# HARDCAL1_REVA_PG3.net
KiCad netlist of a schematic drawn in Altium Designer
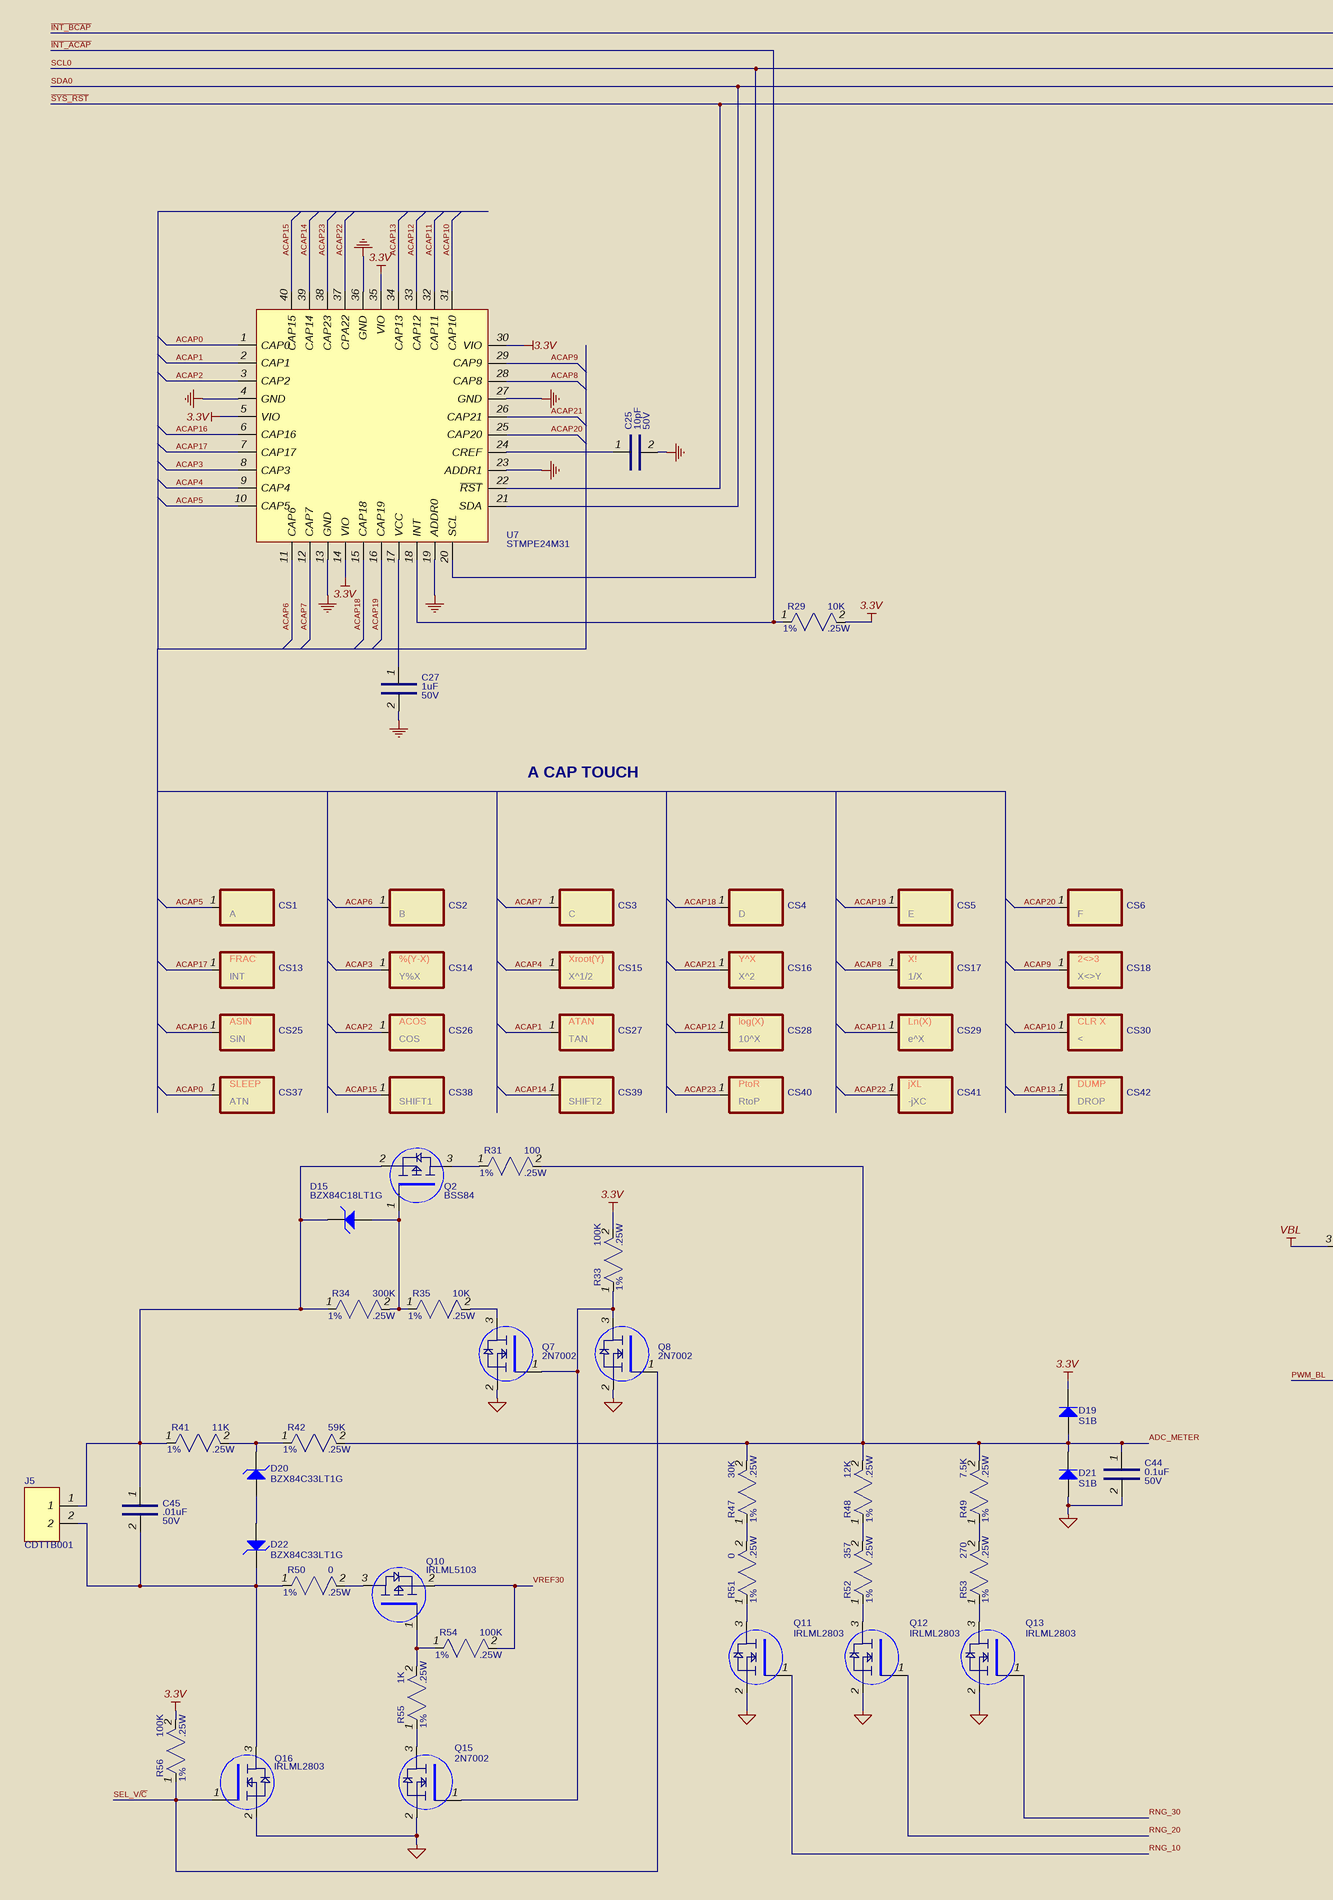
[diagram p0: HARDCAL1_REVA_PG3.SchDoc, left]
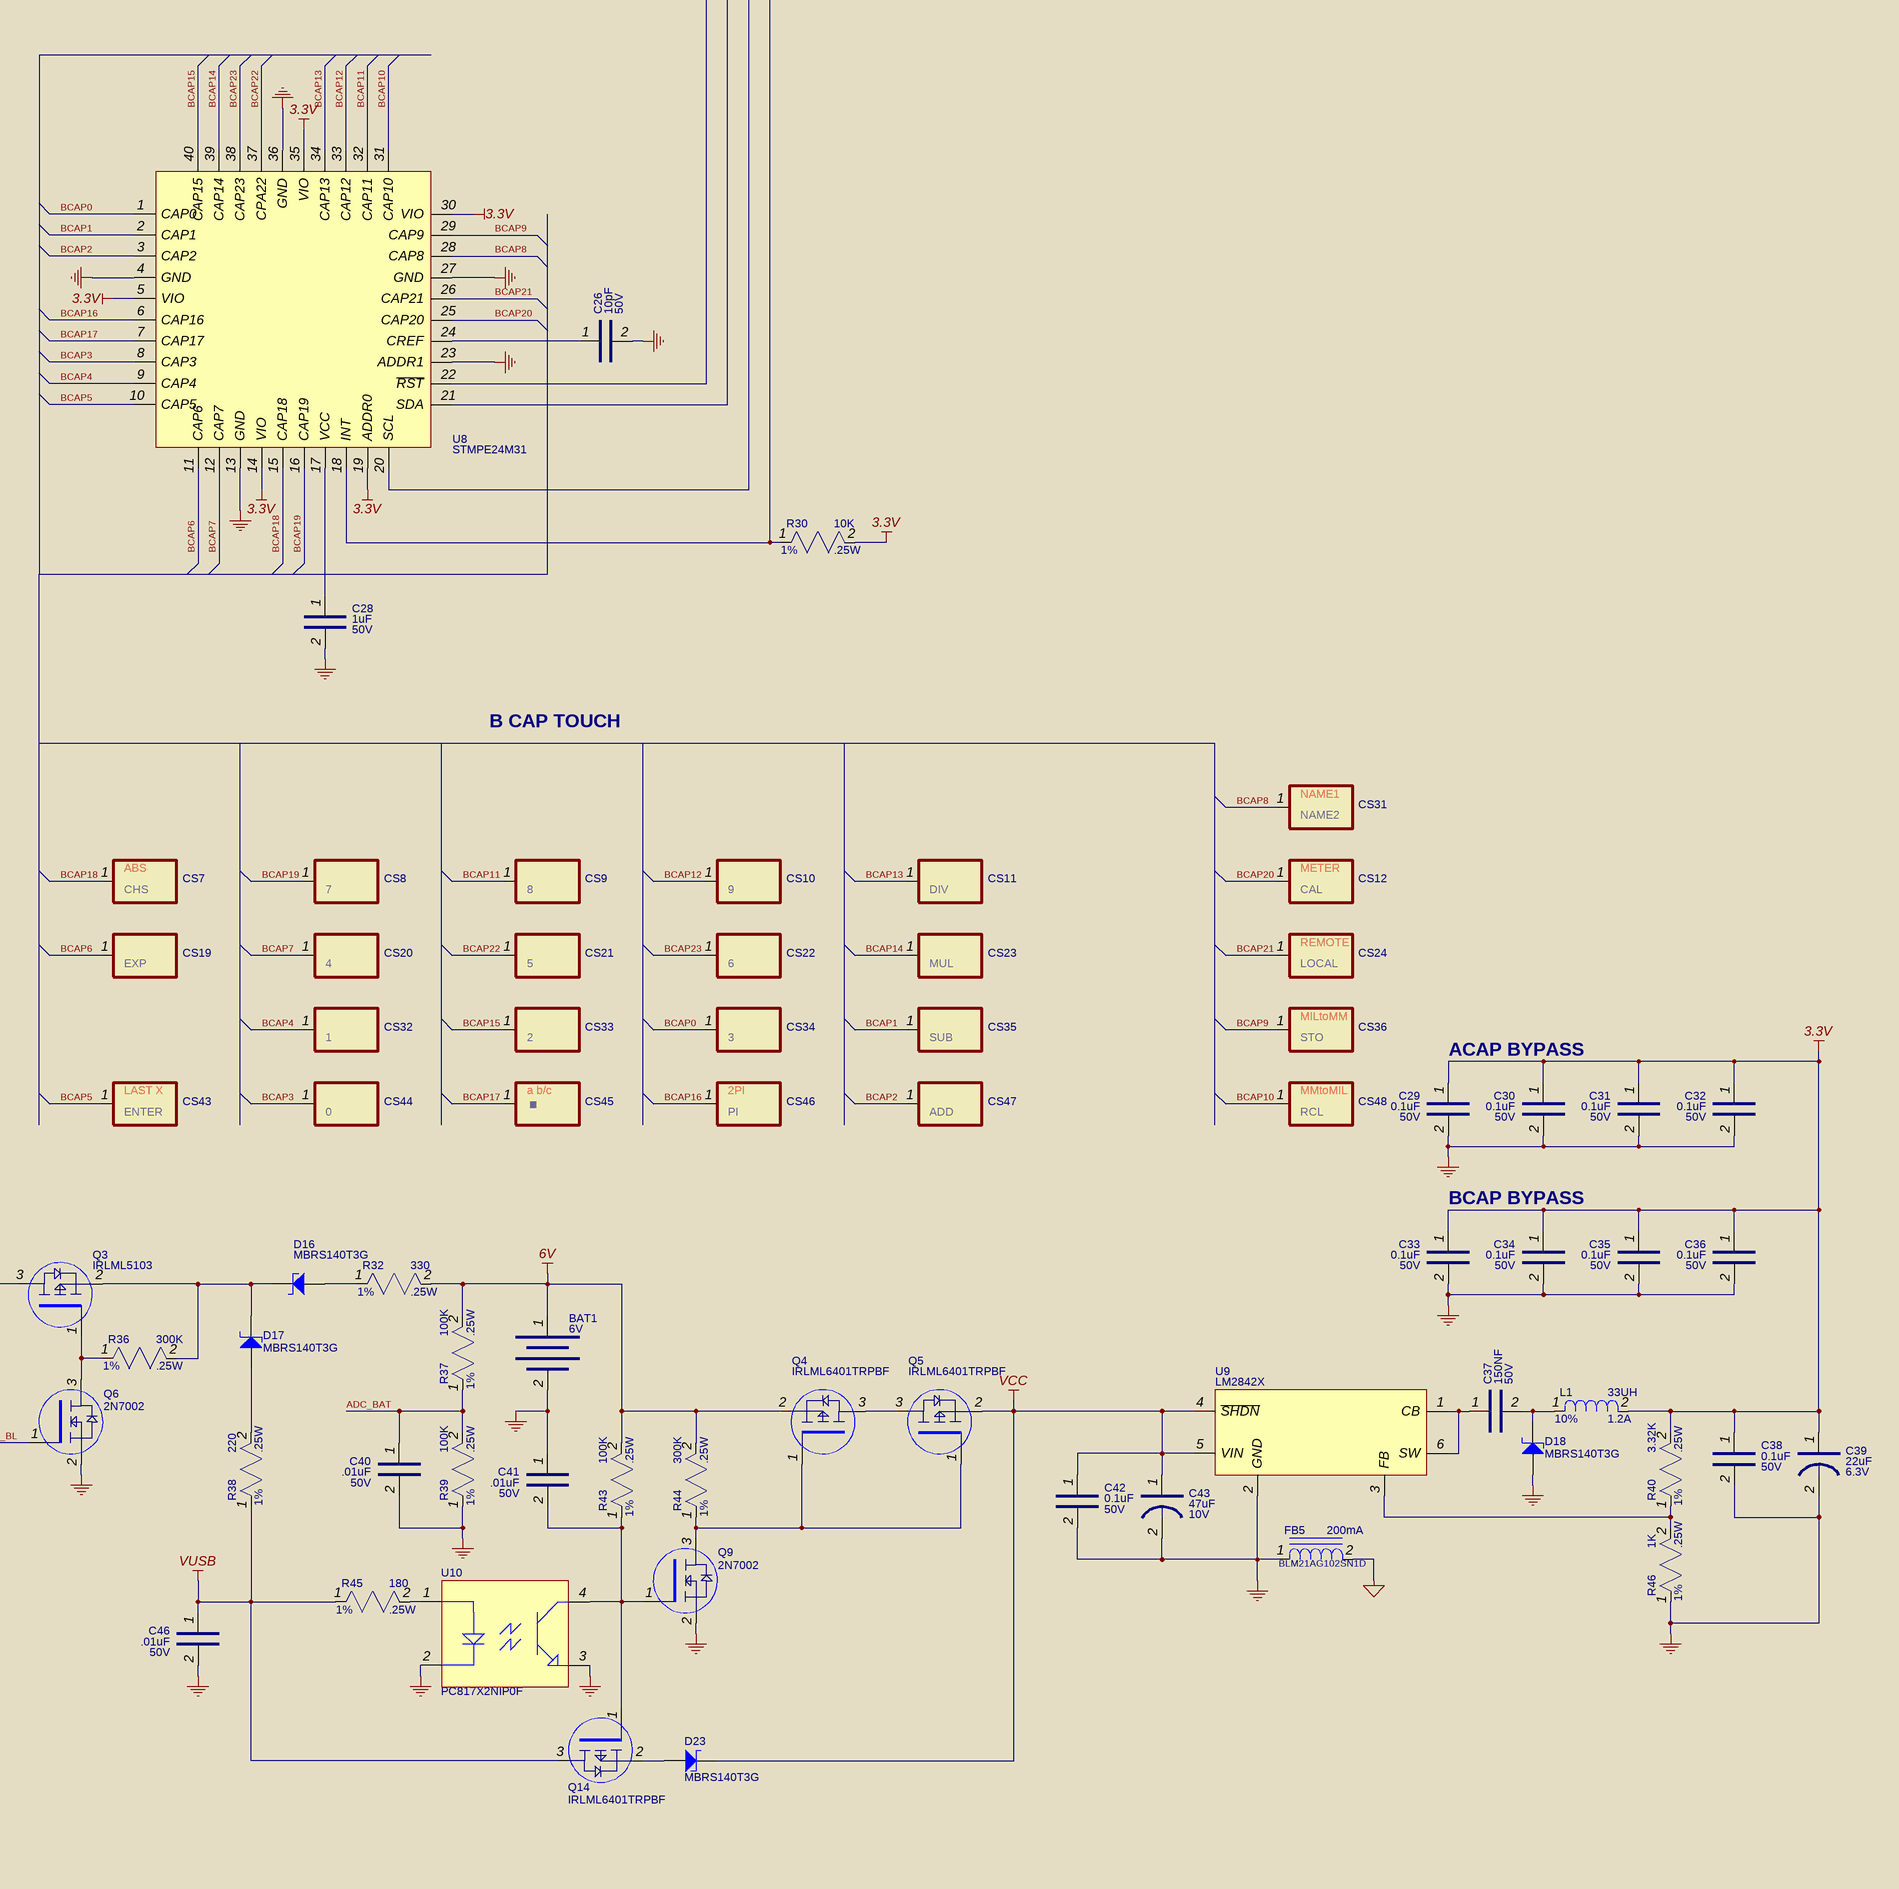
[diagram p1: HARDCAL1_REVA_PG3.SchDoc, right]

(export (version "E")
  (design (tool "Eeschema 10.0.6"))
  (components
    (comp (ref "BAT1")
      (value "CDEVA00082_1")
      (footprint "KEYSTONE_1062")
      (description "CONN, BAT HOLDER 2-COIN CELL 20MM, SMD, ROHS")
      (fields (field (name "MFG") "KEYSTONE ELECTRONICS") (field (name "VOLTAGE") "6V"))
      (libsource (lib "HabLib") (part "CDEVA00082_1"))
    )
    (comp (ref "C25")
      (value "10pF")
      (footprint "3216[1206] - TAN COLOR")
      (description "CAP, CERAMIC, NPO, 10PF, 50V, 1206, 5%, RoHS")
      (fields (field (name "MFG") "AVX") (field (name "TOLERANCE") "10%") (field (name "VOLTAGE") "50V"))
      (libsource (lib "HabLib") (part "CDECA00143"))
    )
    (comp (ref "C26")
      (value "10pF")
      (footprint "3216[1206] - TAN COLOR")
      (description "CAP, CERAMIC, NPO, 10PF, 50V, 1206, 5%, RoHS")
      (fields (field (name "MFG") "AVX") (field (name "TOLERANCE") "10%") (field (name "VOLTAGE") "50V"))
      (libsource (lib "HabLib") (part "CDECA00143"))
    )
    (comp (ref "C27")
      (value "1uF")
      (footprint "3225[1210]")
      (description "CAP, CERAMIC CHIP 1UF 10% 50V X7R ROHS")
      (fields (field (name "MFG") "AVX") (field (name "TOLERANCE") "10%") (field (name "VOLTAGE") "50V"))
      (libsource (lib "HabLib") (part "CDECA00122"))
    )
    (comp (ref "C28")
      (value "1uF")
      (footprint "3225[1210]")
      (description "CAP, CERAMIC CHIP 1UF 10% 50V X7R ROHS")
      (fields (field (name "MFG") "AVX") (field (name "TOLERANCE") "10%") (field (name "VOLTAGE") "50V"))
      (libsource (lib "HabLib") (part "CDECA00122"))
    )
    (comp (ref "C29")
      (value "0.1uF")
      (footprint "3216[1206] - TAN COLOR")
      (description "CAP, CERAMIC CHIP 0.1UF 10% 50V X7R ROHS")
      (fields (field (name "MFG") "AVX") (field (name "TOLERANCE") "10%") (field (name "VOLTAGE") "50V"))
      (libsource (lib "HabLib") (part "CDECA00070"))
    )
    (comp (ref "C30")
      (value "0.1uF")
      (footprint "3216[1206] - TAN COLOR")
      (description "CAP, CERAMIC CHIP 0.1UF 10% 50V X7R ROHS")
      (fields (field (name "MFG") "AVX") (field (name "TOLERANCE") "10%") (field (name "VOLTAGE") "50V"))
      (libsource (lib "HabLib") (part "CDECA00070"))
    )
    (comp (ref "C31")
      (value "0.1uF")
      (footprint "3216[1206] - TAN COLOR")
      (description "CAP, CERAMIC CHIP 0.1UF 10% 50V X7R ROHS")
      (fields (field (name "MFG") "AVX") (field (name "TOLERANCE") "10%") (field (name "VOLTAGE") "50V"))
      (libsource (lib "HabLib") (part "CDECA00070"))
    )
    (comp (ref "C32")
      (value "0.1uF")
      (footprint "3216[1206] - TAN COLOR")
      (description "CAP, CERAMIC CHIP 0.1UF 10% 50V X7R ROHS")
      (fields (field (name "MFG") "AVX") (field (name "TOLERANCE") "10%") (field (name "VOLTAGE") "50V"))
      (libsource (lib "HabLib") (part "CDECA00070"))
    )
    (comp (ref "C33")
      (value "0.1uF")
      (footprint "3216[1206] - TAN COLOR")
      (description "CAP, CERAMIC CHIP 0.1UF 10% 50V X7R ROHS")
      (fields (field (name "MFG") "AVX") (field (name "TOLERANCE") "10%") (field (name "VOLTAGE") "50V"))
      (libsource (lib "HabLib") (part "CDECA00070"))
    )
    (comp (ref "C34")
      (value "0.1uF")
      (footprint "3216[1206] - TAN COLOR")
      (description "CAP, CERAMIC CHIP 0.1UF 10% 50V X7R ROHS")
      (fields (field (name "MFG") "AVX") (field (name "TOLERANCE") "10%") (field (name "VOLTAGE") "50V"))
      (libsource (lib "HabLib") (part "CDECA00070"))
    )
    (comp (ref "C35")
      (value "0.1uF")
      (footprint "3216[1206] - TAN COLOR")
      (description "CAP, CERAMIC CHIP 0.1UF 10% 50V X7R ROHS")
      (fields (field (name "MFG") "AVX") (field (name "TOLERANCE") "10%") (field (name "VOLTAGE") "50V"))
      (libsource (lib "HabLib") (part "CDECA00070"))
    )
    (comp (ref "C36")
      (value "0.1uF")
      (footprint "3216[1206] - TAN COLOR")
      (description "CAP, CERAMIC CHIP 0.1UF 10% 50V X7R ROHS")
      (fields (field (name "MFG") "AVX") (field (name "TOLERANCE") "10%") (field (name "VOLTAGE") "50V"))
      (libsource (lib "HabLib") (part "CDECA00070"))
    )
    (comp (ref "C37")
      (value "150NF")
      (footprint "3216[1206] - TAN COLOR")
      (description "CAP, CERAMIC, X7R, 150NF, 50V, 1206, 10%, RoHS")
      (fields (field (name "MFG") "KEMET") (field (name "TOLERANCE") "10%") (field (name "VOLTAGE") "50V"))
      (libsource (lib "HabLib") (part "CDECA00143_1"))
    )
    (comp (ref "C38")
      (value "0.1uF")
      (footprint "3216[1206] - TAN COLOR")
      (description "CAP, CERAMIC CHIP 0.1UF 10% 50V X7R ROHS")
      (fields (field (name "MFG") "AVX") (field (name "TOLERANCE") "10%") (field (name "VOLTAGE") "50V"))
      (libsource (lib "HabLib") (part "CDECA00070"))
    )
    (comp (ref "C39")
      (value "22uF")
      (footprint "3216[1206] - TANTALUM")
      (description "CAP, TANT, 22UF, 6.3V, 20%, LOW ESR, 1206ROHS")
      (fields (field (name "MFG") "AVX") (field (name "TOLERANCE") "20%") (field (name "VOLTAGE") "6.3V"))
      (libsource (lib "HabLib") (part "CDECA00139_1"))
    )
    (comp (ref "C40")
      (value ".01uF")
      (footprint "3216[1206] - TAN COLOR")
      (description "CAP, CERAMIC CHIP 0.01UF 10% 50V X7R ROHS")
      (fields
        (field (name "MFG") "PANASONIC")
        (field (name "TOLERANCE") "10%")
        (field (name "VOLTAGE") "50V")
      )
      (libsource (lib "HabLib") (part "CDECA00085"))
    )
    (comp (ref "C41")
      (value ".01uF")
      (footprint "3216[1206] - TAN COLOR")
      (description "CAP, CERAMIC CHIP 0.01UF 10% 50V X7R ROHS")
      (fields
        (field (name "MFG") "PANASONIC")
        (field (name "TOLERANCE") "10%")
        (field (name "VOLTAGE") "50V")
      )
      (libsource (lib "HabLib") (part "CDECA00085"))
    )
    (comp (ref "C42")
      (value "0.1uF")
      (footprint "3216[1206] - TAN COLOR")
      (description "CAP, CERAMIC CHIP 0.1UF 10% 50V X7R ROHS")
      (fields (field (name "MFG") "AVX") (field (name "TOLERANCE") "10%") (field (name "VOLTAGE") "50V"))
      (libsource (lib "HabLib") (part "CDECA00070"))
    )
    (comp (ref "C43")
      (value "47uF")
      (footprint "CAP_TANT_3528")
      (description "CAP, TANT, 47UF, 25V, 20%, 3528 ROHS")
      (fields (field (name "MFG") "AVX") (field (name "TOLERANCE") "20%") (field (name "VOLTAGE") "10V"))
      (libsource (lib "HabLib") (part "CDECA00110_1"))
    )
    (comp (ref "C44")
      (value "0.1uF")
      (footprint "3216[1206] - TAN COLOR")
      (description "CAP, CERAMIC CHIP 0.1UF 10% 50V X7R ROHS")
      (fields (field (name "MFG") "AVX") (field (name "TOLERANCE") "10%") (field (name "VOLTAGE") "50V"))
      (libsource (lib "HabLib") (part "CDECA00070"))
    )
    (comp (ref "C45")
      (value ".01uF")
      (footprint "3216[1206] - TAN COLOR")
      (description "CAP, CERAMIC CHIP 0.01UF 10% 50V X7R ROHS")
      (fields
        (field (name "MFG") "PANASONIC")
        (field (name "TOLERANCE") "10%")
        (field (name "VOLTAGE") "50V")
      )
      (libsource (lib "") (part "CDECA00085_1"))
    )
    (comp (ref "C46")
      (value ".01uF")
      (footprint "3216[1206] - TAN COLOR")
      (description "CAP, CERAMIC CHIP 0.01UF 10% 50V X7R ROHS")
      (fields
        (field (name "MFG") "PANASONIC")
        (field (name "TOLERANCE") "10%")
        (field (name "VOLTAGE") "50V")
      )
      (libsource (lib "HabLib") (part "CDECA00085"))
    )
    (comp (ref "CS1")
      (value "CAP_SENSOR")
      (footprint "CAPTOUCH1_10X10")
      (description "CAP SENSOR FOR PCB")
      (fields (field (name "VALUE2") "A") (field (name "PUBLISHER") "Altium Limited"))
      (libsource (lib "HabLib") (part "CAP_SENSOR"))
    )
    (comp (ref "CS2")
      (value "CAP_SENSOR")
      (footprint "CAPTOUCH1_10X10")
      (description "CAP SENSOR FOR PCB")
      (fields (field (name "VALUE2") "B") (field (name "PUBLISHER") "Altium Limited"))
      (libsource (lib "HabLib") (part "CAP_SENSOR"))
    )
    (comp (ref "CS3")
      (value "CAP_SENSOR")
      (footprint "CAPTOUCH1_10X10")
      (description "CAP SENSOR FOR PCB")
      (fields (field (name "VALUE2") "C") (field (name "PUBLISHER") "Altium Limited"))
      (libsource (lib "HabLib") (part "CAP_SENSOR"))
    )
    (comp (ref "CS4")
      (value "CAP_SENSOR")
      (footprint "CAPTOUCH1_10X10")
      (description "CAP SENSOR FOR PCB")
      (fields (field (name "VALUE2") "D") (field (name "PUBLISHER") "Altium Limited"))
      (libsource (lib "HabLib") (part "CAP_SENSOR"))
    )
    (comp (ref "CS5")
      (value "CAP_SENSOR")
      (footprint "CAPTOUCH1_10X10")
      (description "CAP SENSOR FOR PCB")
      (fields (field (name "VALUE2") "E") (field (name "PUBLISHER") "Altium Limited"))
      (libsource (lib "HabLib") (part "CAP_SENSOR"))
    )
    (comp (ref "CS6")
      (value "CAP_SENSOR")
      (footprint "CAPTOUCH1_10X10")
      (description "CAP SENSOR FOR PCB")
      (fields (field (name "VALUE2") "F") (field (name "PUBLISHER") "Altium Limited"))
      (libsource (lib "HabLib") (part "CAP_SENSOR"))
    )
    (comp (ref "CS7")
      (value "ABS")
      (footprint "CAPTOUCH1_10X10")
      (description "CAP SENSOR FOR PCB")
      (fields
        (field (name "VALUE2") "CHS")
        (field (name "Comment") "CAP_SENSOR")
        (field (name "PUBLISHER") "Altium Limited")
      )
      (libsource (lib "HabLib") (part "CAP_SENSOR"))
    )
    (comp (ref "CS8")
      (value "CAP_SENSOR")
      (footprint "CAPTOUCH1_10X10")
      (description "CAP SENSOR FOR PCB")
      (fields (field (name "VALUE2") "7") (field (name "PUBLISHER") "Altium Limited"))
      (libsource (lib "HabLib") (part "CAP_SENSOR"))
    )
    (comp (ref "CS9")
      (value "CAP_SENSOR")
      (footprint "CAPTOUCH1_10X10")
      (description "CAP SENSOR FOR PCB")
      (fields (field (name "VALUE2") "8") (field (name "PUBLISHER") "Altium Limited"))
      (libsource (lib "HabLib") (part "CAP_SENSOR"))
    )
    (comp (ref "CS10")
      (value "CAP_SENSOR")
      (footprint "CAPTOUCH1_10X10")
      (description "CAP SENSOR FOR PCB")
      (fields (field (name "VALUE2") "9") (field (name "PUBLISHER") "Altium Limited"))
      (libsource (lib "HabLib") (part "CAP_SENSOR"))
    )
    (comp (ref "CS11")
      (value "CAP_SENSOR")
      (footprint "CAPTOUCH1_10X10")
      (description "CAP SENSOR FOR PCB")
      (fields (field (name "VALUE2") "DIV") (field (name "PUBLISHER") "Altium Limited"))
      (libsource (lib "HabLib") (part "CAP_SENSOR"))
    )
    (comp (ref "CS12")
      (value "METER")
      (footprint "CAPTOUCH1_10X10")
      (description "CAP SENSOR FOR PCB")
      (fields
        (field (name "VALUE2") "CAL")
        (field (name "Comment") "CAP_SENSOR")
        (field (name "PUBLISHER") "Altium Limited")
      )
      (libsource (lib "HabLib") (part "CAP_SENSOR"))
    )
    (comp (ref "CS13")
      (value "FRAC")
      (footprint "CAPTOUCH1_10X10")
      (description "CAP SENSOR FOR PCB")
      (fields
        (field (name "VALUE2") "INT")
        (field (name "Comment") "CAP_SENSOR")
        (field (name "PUBLISHER") "Altium Limited")
      )
      (libsource (lib "HabLib") (part "CAP_SENSOR"))
    )
    (comp (ref "CS14")
      (value "%(Y-X)")
      (footprint "CAPTOUCH1_10X10")
      (description "CAP SENSOR FOR PCB")
      (fields
        (field (name "VALUE2") "Y%X")
        (field (name "Comment") "CAP_SENSOR")
        (field (name "PUBLISHER") "Altium Limited")
      )
      (libsource (lib "HabLib") (part "CAP_SENSOR"))
    )
    (comp (ref "CS15")
      (value "Xroot(Y)")
      (footprint "CAPTOUCH1_10X10")
      (description "CAP SENSOR FOR PCB")
      (fields
        (field (name "VALUE2") "X^1/2")
        (field (name "Comment") "CAP_SENSOR")
        (field (name "PUBLISHER") "Altium Limited")
      )
      (libsource (lib "HabLib") (part "CAP_SENSOR"))
    )
    (comp (ref "CS16")
      (value "Y^X")
      (footprint "CAPTOUCH1_10X10")
      (description "CAP SENSOR FOR PCB")
      (fields
        (field (name "VALUE2") "X^2")
        (field (name "Comment") "CAP_SENSOR")
        (field (name "PUBLISHER") "Altium Limited")
      )
      (libsource (lib "HabLib") (part "CAP_SENSOR"))
    )
    (comp (ref "CS17")
      (value "X!")
      (footprint "CAPTOUCH1_10X10")
      (description "CAP SENSOR FOR PCB")
      (fields
        (field (name "VALUE2") "1/X")
        (field (name "Comment") "CAP_SENSOR")
        (field (name "PUBLISHER") "Altium Limited")
      )
      (libsource (lib "HabLib") (part "CAP_SENSOR"))
    )
    (comp (ref "CS18")
      (value "2<>3")
      (footprint "CAPTOUCH1_10X10")
      (description "CAP SENSOR FOR PCB")
      (fields
        (field (name "VALUE2") "X<>Y")
        (field (name "Comment") "CAP_SENSOR")
        (field (name "PUBLISHER") "Altium Limited")
      )
      (libsource (lib "HabLib") (part "CAP_SENSOR"))
    )
    (comp (ref "CS19")
      (value "CAP_SENSOR")
      (footprint "CAPTOUCH1_10X10")
      (description "CAP SENSOR FOR PCB")
      (fields (field (name "VALUE2") "EXP") (field (name "PUBLISHER") "Altium Limited"))
      (libsource (lib "HabLib") (part "CAP_SENSOR"))
    )
    (comp (ref "CS20")
      (value "CAP_SENSOR")
      (footprint "CAPTOUCH1_10X10")
      (description "CAP SENSOR FOR PCB")
      (fields (field (name "VALUE2") "4") (field (name "PUBLISHER") "Altium Limited"))
      (libsource (lib "HabLib") (part "CAP_SENSOR"))
    )
    (comp (ref "CS21")
      (value "CAP_SENSOR")
      (footprint "CAPTOUCH1_10X10")
      (description "CAP SENSOR FOR PCB")
      (fields (field (name "VALUE2") "5") (field (name "PUBLISHER") "Altium Limited"))
      (libsource (lib "HabLib") (part "CAP_SENSOR"))
    )
    (comp (ref "CS22")
      (value "CAP_SENSOR")
      (footprint "CAPTOUCH1_10X10")
      (description "CAP SENSOR FOR PCB")
      (fields (field (name "VALUE2") "6") (field (name "PUBLISHER") "Altium Limited"))
      (libsource (lib "HabLib") (part "CAP_SENSOR"))
    )
    (comp (ref "CS23")
      (value "CAP_SENSOR")
      (footprint "CAPTOUCH1_10X10")
      (description "CAP SENSOR FOR PCB")
      (fields (field (name "VALUE2") "MUL") (field (name "PUBLISHER") "Altium Limited"))
      (libsource (lib "HabLib") (part "CAP_SENSOR"))
    )
    (comp (ref "CS24")
      (value "REMOTE")
      (footprint "CAPTOUCH1_10X10")
      (description "CAP SENSOR FOR PCB")
      (fields
        (field (name "VALUE2") "LOCAL")
        (field (name "Comment") "CAP_SENSOR")
        (field (name "PUBLISHER") "Altium Limited")
      )
      (libsource (lib "HabLib") (part "CAP_SENSOR"))
    )
    (comp (ref "CS25")
      (value "ASIN")
      (footprint "CAPTOUCH1_10X10")
      (description "CAP SENSOR FOR PCB")
      (fields
        (field (name "VALUE2") "SIN")
        (field (name "Comment") "CAP_SENSOR")
        (field (name "PUBLISHER") "Altium Limited")
      )
      (libsource (lib "HabLib") (part "CAP_SENSOR"))
    )
    (comp (ref "CS26")
      (value "ACOS")
      (footprint "CAPTOUCH1_10X10")
      (description "CAP SENSOR FOR PCB")
      (fields
        (field (name "VALUE2") "COS")
        (field (name "Comment") "CAP_SENSOR")
        (field (name "PUBLISHER") "Altium Limited")
      )
      (libsource (lib "HabLib") (part "CAP_SENSOR"))
    )
    (comp (ref "CS27")
      (value "ATAN")
      (footprint "CAPTOUCH1_10X10")
      (description "CAP SENSOR FOR PCB")
      (fields
        (field (name "VALUE2") "TAN")
        (field (name "Comment") "CAP_SENSOR")
        (field (name "PUBLISHER") "Altium Limited")
      )
      (libsource (lib "HabLib") (part "CAP_SENSOR"))
    )
    (comp (ref "CS28")
      (value "log(X)")
      (footprint "CAPTOUCH1_10X10")
      (description "CAP SENSOR FOR PCB")
      (fields
        (field (name "VALUE2") "10^X")
        (field (name "Comment") "CAP_SENSOR")
        (field (name "PUBLISHER") "Altium Limited")
      )
      (libsource (lib "HabLib") (part "CAP_SENSOR"))
    )
    (comp (ref "CS29")
      (value "Ln(X)")
      (footprint "CAPTOUCH1_10X10")
      (description "CAP SENSOR FOR PCB")
      (fields
        (field (name "VALUE2") "e^X")
        (field (name "Comment") "CAP_SENSOR")
        (field (name "PUBLISHER") "Altium Limited")
      )
      (libsource (lib "HabLib") (part "CAP_SENSOR"))
    )
    (comp (ref "CS30")
      (value "CLR X")
      (footprint "CAPTOUCH1_10X10")
      (description "CAP SENSOR FOR PCB")
      (fields
        (field (name "VALUE2") "<")
        (field (name "Comment") "CAP_SENSOR")
        (field (name "PUBLISHER") "Altium Limited")
      )
      (libsource (lib "HabLib") (part "CAP_SENSOR"))
    )
    (comp (ref "CS31")
      (value "NAME1")
      (footprint "CAPTOUCH1_10X10")
      (description "CAP SENSOR FOR PCB")
      (fields
        (field (name "VALUE2") "NAME2")
        (field (name "Comment") "CAP_SENSOR")
        (field (name "PUBLISHER") "Altium Limited")
      )
      (libsource (lib "HabLib") (part "CAP_SENSOR"))
    )
    (comp (ref "CS32")
      (value "CAP_SENSOR")
      (footprint "CAPTOUCH1_10X10")
      (description "CAP SENSOR FOR PCB")
      (fields (field (name "VALUE2") "1") (field (name "PUBLISHER") "Altium Limited"))
      (libsource (lib "HabLib") (part "CAP_SENSOR"))
    )
    (comp (ref "CS33")
      (value "CAP_SENSOR")
      (footprint "CAPTOUCH1_10X10")
      (description "CAP SENSOR FOR PCB")
      (fields (field (name "VALUE2") "2") (field (name "PUBLISHER") "Altium Limited"))
      (libsource (lib "HabLib") (part "CAP_SENSOR"))
    )
    (comp (ref "CS34")
      (value "CAP_SENSOR")
      (footprint "CAPTOUCH1_10X10")
      (description "CAP SENSOR FOR PCB")
      (fields (field (name "VALUE2") "3") (field (name "PUBLISHER") "Altium Limited"))
      (libsource (lib "HabLib") (part "CAP_SENSOR"))
    )
    (comp (ref "CS35")
      (value "CAP_SENSOR")
      (footprint "CAPTOUCH1_10X10")
      (description "CAP SENSOR FOR PCB")
      (fields (field (name "VALUE2") "SUB") (field (name "PUBLISHER") "Altium Limited"))
      (libsource (lib "HabLib") (part "CAP_SENSOR"))
    )
    (comp (ref "CS36")
      (value "MILtoMM")
      (footprint "CAPTOUCH1_10X10")
      (description "CAP SENSOR FOR PCB")
      (fields
        (field (name "VALUE2") "STO")
        (field (name "Comment") "CAP_SENSOR")
        (field (name "PUBLISHER") "Altium Limited")
      )
      (libsource (lib "HabLib") (part "CAP_SENSOR"))
    )
    (comp (ref "CS37")
      (value "SLEEP")
      (footprint "CAPTOUCH1_10X10")
      (description "CAP SENSOR FOR PCB")
      (fields
        (field (name "VALUE2") "ATN")
        (field (name "Comment") "CAP_SENSOR")
        (field (name "PUBLISHER") "Altium Limited")
      )
      (libsource (lib "HabLib") (part "CAP_SENSOR"))
    )
    (comp (ref "CS38")
      (value "CAP_SENSOR")
      (footprint "CAPTOUCH1_10X10")
      (description "CAP SENSOR FOR PCB")
      (fields (field (name "VALUE2") "SHIFT1") (field (name "PUBLISHER") "Altium Limited"))
      (libsource (lib "HabLib") (part "CAP_SENSOR"))
    )
    (comp (ref "CS39")
      (value "CAP_SENSOR")
      (footprint "CAPTOUCH1_10X10")
      (description "CAP SENSOR FOR PCB")
      (fields (field (name "VALUE2") "SHIFT2") (field (name "PUBLISHER") "Altium Limited"))
      (libsource (lib "HabLib") (part "CAP_SENSOR"))
    )
    (comp (ref "CS40")
      (value "PtoR")
      (footprint "CAPTOUCH1_10X10")
      (description "CAP SENSOR FOR PCB")
      (fields
        (field (name "VALUE2") "RtoP")
        (field (name "Comment") "CAP_SENSOR")
        (field (name "PUBLISHER") "Altium Limited")
      )
      (libsource (lib "HabLib") (part "CAP_SENSOR"))
    )
    (comp (ref "CS41")
      (value "jXL")
      (footprint "CAPTOUCH1_10X10")
      (description "CAP SENSOR FOR PCB")
      (fields
        (field (name "VALUE2") "-jXC")
        (field (name "Comment") "CAP_SENSOR")
        (field (name "PUBLISHER") "Altium Limited")
      )
      (libsource (lib "HabLib") (part "CAP_SENSOR"))
    )
    (comp (ref "CS42")
      (value "DUMP")
      (footprint "CAPTOUCH1_10X10")
      (description "CAP SENSOR FOR PCB")
      (fields
        (field (name "VALUE2") "DROP")
        (field (name "Comment") "CAP_SENSOR")
        (field (name "PUBLISHER") "Altium Limited")
      )
      (libsource (lib "HabLib") (part "CAP_SENSOR"))
    )
    (comp (ref "CS43")
      (value "LAST X")
      (footprint "CAPTOUCH1_10X23")
      (description "CAP SENSOR FOR PCB")
      (fields
        (field (name "VALUE2") "ENTER")
        (field (name "Comment") "CAP_SENSOR_ENT")
        (field (name "PUBLISHER") "Altium Limited")
      )
      (libsource (lib "HabLib") (part "CAP_SENSOR_ENT"))
    )
    (comp (ref "CS44")
      (value "CAP_SENSOR")
      (footprint "CAPTOUCH1_10X10")
      (description "CAP SENSOR FOR PCB")
      (fields (field (name "VALUE2") "0") (field (name "PUBLISHER") "Altium Limited"))
      (libsource (lib "HabLib") (part "CAP_SENSOR"))
    )
    (comp (ref "CS45")
      (value "a b/c")
      (footprint "CAPTOUCH1_10X10")
      (description "CAP SENSOR FOR PCB")
      (fields
        (field (name "VALUE2") ".")
        (field (name "Comment") "CAP_SENSOR")
        (field (name "PUBLISHER") "Altium Limited")
      )
      (libsource (lib "HabLib") (part "CAP_SENSOR"))
    )
    (comp (ref "CS46")
      (value "2PI")
      (footprint "CAPTOUCH1_10X10")
      (description "CAP SENSOR FOR PCB")
      (fields
        (field (name "VALUE2") "PI")
        (field (name "Comment") "CAP_SENSOR")
        (field (name "PUBLISHER") "Altium Limited")
      )
      (libsource (lib "HabLib") (part "CAP_SENSOR"))
    )
    (comp (ref "CS47")
      (value "CAP_SENSOR")
      (footprint "CAPTOUCH1_10X10")
      (description "CAP SENSOR FOR PCB")
      (fields (field (name "VALUE2") "ADD") (field (name "PUBLISHER") "Altium Limited"))
      (libsource (lib "HabLib") (part "CAP_SENSOR"))
    )
    (comp (ref "CS48")
      (value "MMtoMIL")
      (footprint "CAPTOUCH1_10X10")
      (description "CAP SENSOR FOR PCB")
      (fields
        (field (name "VALUE2") "RCL")
        (field (name "Comment") "CAP_SENSOR")
        (field (name "PUBLISHER") "Altium Limited")
      )
      (libsource (lib "HabLib") (part "CAP_SENSOR"))
    )
    (comp (ref "D15")
      (value "BZX84C18LT1G")
      (footprint "SOT23 - TRANSISTOR")
      (description "DIODE, ZENER, 18V, 225MW, SOT-23, ROHS")
      (fields (field (name "MFG") "ON SEMICONDUCTOR") (field (name "Comment") "CDEDA00055_1"))
      (libsource (lib "HabLib") (part "CDEDA00055_1"))
    )
    (comp (ref "D16")
      (value "MBRS140T3G")
      (footprint "DIODE_SMB")
      (description "Diode, Schottky rectifier, 40V, 1A, SMB package, Pb free")
      (fields
        (field (name "MFG") "ON SEMICONDUCTOR")
        (field (name "Comment") "CDEDA00019")
        (field (name "PUBLISHER") "Altium Limited")
      )
      (libsource (lib "HabLib") (part "CDEDA00019"))
    )
    (comp (ref "D17")
      (value "MBRS140T3G")
      (footprint "DIODE_SMB")
      (description "Diode, Schottky rectifier, 40V, 1A, SMB package, Pb free")
      (fields
        (field (name "MFG") "ON SEMICONDUCTOR")
        (field (name "Comment") "CDEDA00019")
        (field (name "PUBLISHER") "Altium Limited")
      )
      (libsource (lib "HabLib") (part "CDEDA00019"))
    )
    (comp (ref "D18")
      (value "MBRS140T3G")
      (footprint "DIODE_SMB")
      (description "Diode, Schottky rectifier, 40V, 1A, SMB package, Pb free")
      (fields
        (field (name "MFG") "ON SEMICONDUCTOR")
        (field (name "Comment") "CDEDA00019")
        (field (name "PUBLISHER") "Altium Limited")
      )
      (libsource (lib "HabLib") (part "CDEDA00019"))
    )
    (comp (ref "D19")
      (value "S1B")
      (footprint "DIODE SMA")
      (description "DIODE, 1A, 100V, SMA, ROHS")
      (fields (field (name "MFG") "FAIRCHILD SEMICONDUCTOR") (field (name "Comment") "CDEDA00055_3"))
      (libsource (lib "HabLib") (part "CDEDA00055_3"))
    )
    (comp (ref "D20")
      (value "BZX84C33LT1G")
      (footprint "SOT23 - TRANSISTOR")
      (description "DIODE, ZENER, 33V, 225MW, SOT-23, ROHS")
      (fields (field (name "MFG") "ON SEMICONDUCTOR") (field (name "Comment") "CDEDA00055_2"))
      (libsource (lib "HabLib") (part "CDEDA00055_2"))
    )
    (comp (ref "D21")
      (value "S1B")
      (footprint "DIODE SMA")
      (description "DIODE, 1A, 100V, SMA, ROHS")
      (fields (field (name "MFG") "FAIRCHILD SEMICONDUCTOR") (field (name "Comment") "CDEDA00055_3"))
      (libsource (lib "HabLib") (part "CDEDA00055_3"))
    )
    (comp (ref "D22")
      (value "BZX84C33LT1G")
      (footprint "SOT23 - TRANSISTOR")
      (description "DIODE, ZENER, 33V, 225MW, SOT-23, ROHS")
      (fields (field (name "MFG") "ON SEMICONDUCTOR") (field (name "Comment") "CDEDA00055_2"))
      (libsource (lib "HabLib") (part "CDEDA00055_2"))
    )
    (comp (ref "D23")
      (value "MBRS140T3G")
      (footprint "DIODE_SMB")
      (description "Diode, Schottky rectifier, 40V, 1A, SMB package, Pb free")
      (fields
        (field (name "MFG") "ON SEMICONDUCTOR")
        (field (name "Comment") "CDEDA00019")
        (field (name "PUBLISHER") "Altium Limited")
      )
      (libsource (lib "HabLib") (part "CDEDA00019"))
    )
    (comp (ref "FB5")
      (value "CDEVA00115")
      (footprint "2012[0805]")
      (description "FERRITE, 1KOHM AT 100MHZ, 220MA, .450DCR")
      (fields
        (field (name "MFG") "MURATA")
        (field (name "TOLERANCE") "10%")
        (field (name "MFG_PN") "BLM21AG102SN1D")
        (field (name "POWER") "200mA")
        (field (name "PUBLISHER") "Altium Limited")
      )
      (libsource (lib "HabLib") (part "CDEVA00115"))
    )
    (comp (ref "J5")
      (value "CDTTB001")
      (footprint "PHOENIX_CONTACT_1933189")
      (description "CONN, HDR, 2PIN, 5MM PHONIX CONTACT, ROHS")
      (fields (field (name "MFG") "PHOENIX CONTACT"))
      (libsource (lib "HabLib") (part "CDTTB001"))
    )
    (comp (ref "L1")
      (value "33UH")
      (footprint "BOURNS_SDR0805-XXXX")
      (description "INDUCTOR, 33UH, 10%, SMT, NON-SHIELDED, FERRITE CORE, ROHS")
      (fields
        (field (name "MFG") "BOURNS")
        (field (name "TOLERANCE") "10%")
        (field (name "POWER") "1.2A")
        (field (name "Comment") "CDEHA00005_1")
      )
      (libsource (lib "HabLib") (part "CDEHA00005_1"))
    )
    (comp (ref "Q2")
      (value "BSS84")
      (footprint "SOT23 - TRANSISTOR")
      (description "MOSFET P CHN, VDS=50V, RDSON = 10OHM, SOT 23")
      (fields
        (field (name "MFG") "DIODES INC")
        (field (name "Comment") "CDENA00031_1")
        (field (name "PUBLISHER") "Altium Limited")
      )
      (libsource (lib "HabLib") (part "CDENA00031_1"))
    )
    (comp (ref "Q3")
      (value "IRLML5103")
      (footprint "SOT23 - TRANSISTOR")
      (description "MOSFET P CHN, VDS=30V, RDSON = .6OHM, SOT 23")
      (fields
        (field (name "MFG") "INTERNATIONAL RECTIFIER")
        (field (name "Comment") "CDENA00031")
        (field (name "PUBLISHER") "Altium Limited")
      )
      (libsource (lib "HabLib") (part "CDENA00031"))
    )
    (comp (ref "Q4")
      (value "IRLML6401TRPBF")
      (footprint "SOT23 - TRANSISTOR")
      (description "MOSFET P CHN, VDS=12V, RDSON = .05OHM, SOT 23")
      (fields
        (field (name "MFG") "INTERNATIONAL RECTIFIER")
        (field (name "Comment") "CDENA00031_3")
        (field (name "PUBLISHER") "Altium Limited")
      )
      (libsource (lib "HabLib") (part "CDENA00031_3"))
    )
    (comp (ref "Q5")
      (value "IRLML6401TRPBF")
      (footprint "SOT23 - TRANSISTOR")
      (description "MOSFET P CHN, VDS=12V, RDSON = .05OHM, SOT 23")
      (fields
        (field (name "MFG") "INTERNATIONAL RECTIFIER")
        (field (name "Comment") "CDENA00031_3")
        (field (name "PUBLISHER") "Altium Limited")
      )
      (libsource (lib "") (part "CDENA00031_3_1"))
    )
    (comp (ref "Q6")
      (value "2N7002")
      (footprint "SOT23 - TRANSISTOR")
      (description "MOSFET N CHN, VDS=60V, 115 mA, SOT 23")
      (fields
        (field (name "MFG") "DIODES INC")
        (field (name "Comment") "CDENA00030")
        (field (name "PUBLISHER") "Altium Limited")
      )
      (libsource (lib "HabLib") (part "CDENA00030"))
    )
    (comp (ref "Q7")
      (value "2N7002")
      (footprint "SOT23 - TRANSISTOR")
      (description "MOSFET N CHN, VDS=60V, 115 mA, SOT 23")
      (fields
        (field (name "MFG") "DIODES INC")
        (field (name "Comment") "CDENA00030")
        (field (name "PUBLISHER") "Altium Limited")
      )
      (libsource (lib "") (part "CDENA00030_1"))
    )
    (comp (ref "Q8")
      (value "2N7002")
      (footprint "SOT23 - TRANSISTOR")
      (description "MOSFET N CHN, VDS=60V, 115 mA, SOT 23")
      (fields
        (field (name "MFG") "DIODES INC")
        (field (name "Comment") "CDENA00030")
        (field (name "PUBLISHER") "Altium Limited")
      )
      (libsource (lib "") (part "CDENA00030_1"))
    )
    (comp (ref "Q9")
      (value "2N7002")
      (footprint "SOT23 - TRANSISTOR")
      (description "MOSFET N CHN, VDS=60V, 115 mA, SOT 23")
      (fields
        (field (name "MFG") "DIODES INC")
        (field (name "Comment") "CDENA00030")
        (field (name "PUBLISHER") "Altium Limited")
      )
      (libsource (lib "HabLib") (part "CDENA00030"))
    )
    (comp (ref "Q10")
      (value "IRLML5103")
      (footprint "SOT23 - TRANSISTOR")
      (description "MOSFET P CHN, VDS=30V, RDSON = .6OHM, SOT 23")
      (fields
        (field (name "MFG") "INTERNATIONAL RECTIFIER")
        (field (name "Comment") "CDENA00031")
        (field (name "PUBLISHER") "Altium Limited")
      )
      (libsource (lib "HabLib") (part "CDENA00031"))
    )
    (comp (ref "Q11")
      (value "IRLML2803")
      (footprint "SOT23 - TRANSISTOR")
      (description "MOSFET N CHN, VDS=60V, 115 mA, SOT 23")
      (fields
        (field (name "MFG") "INTERNATIONAL RECTIFIER")
        (field (name "Comment") "CDENA00031_2")
        (field (name "PUBLISHER") "Altium Limited")
      )
      (libsource (lib "HabLib") (part "CDENA00031_2"))
    )
    (comp (ref "Q12")
      (value "IRLML2803")
      (footprint "SOT23 - TRANSISTOR")
      (description "MOSFET N CHN, VDS=60V, 115 mA, SOT 23")
      (fields
        (field (name "MFG") "INTERNATIONAL RECTIFIER")
        (field (name "Comment") "CDENA00031_2")
        (field (name "PUBLISHER") "Altium Limited")
      )
      (libsource (lib "HabLib") (part "CDENA00031_2"))
    )
    (comp (ref "Q13")
      (value "IRLML2803")
      (footprint "SOT23 - TRANSISTOR")
      (description "MOSFET N CHN, VDS=60V, 115 mA, SOT 23")
      (fields
        (field (name "MFG") "INTERNATIONAL RECTIFIER")
        (field (name "Comment") "CDENA00031_2")
        (field (name "PUBLISHER") "Altium Limited")
      )
      (libsource (lib "HabLib") (part "CDENA00031_2"))
    )
    (comp (ref "Q14")
      (value "IRLML6401TRPBF")
      (footprint "SOT23 - TRANSISTOR")
      (description "MOSFET P CHN, VDS=12V, RDSON = .05OHM, SOT 23")
      (fields
        (field (name "MFG") "INTERNATIONAL RECTIFIER")
        (field (name "Comment") "CDENA00031_3")
        (field (name "PUBLISHER") "Altium Limited")
      )
      (libsource (lib "HabLib") (part "CDENA00031_3"))
    )
    (comp (ref "Q15")
      (value "2N7002")
      (footprint "SOT23 - TRANSISTOR")
      (description "MOSFET N CHN, VDS=60V, 115 mA, SOT 23")
      (fields
        (field (name "MFG") "DIODES INC")
        (field (name "Comment") "CDENA00030")
        (field (name "PUBLISHER") "Altium Limited")
      )
      (libsource (lib "") (part "CDENA00030_1"))
    )
    (comp (ref "Q16")
      (value "IRLML2803")
      (footprint "SOT23 - TRANSISTOR")
      (description "MOSFET N CHN, VDS=60V, 115 mA, SOT 23")
      (fields
        (field (name "MFG") "INTERNATIONAL RECTIFIER")
        (field (name "Comment") "CDENA00031_2")
        (field (name "PUBLISHER") "Altium Limited")
      )
      (libsource (lib "") (part "CDENA00031_2_1"))
    )
    (comp (ref "R29")
      (value "10K")
      (footprint "HabLib:3216[1206]")
      (description "RESISTOR, CHIP 1206 10K OHM 1% 1/4W THICK FILM ROHS")
      (fields
        (field (name "MFG") "PANASONIC")
        (field (name "TOLERANCE") "1%")
        (field (name "POWER") ".25W")
        (field (name "Comment") "CDERA00170")
        (field (name "PUBLISHER") "Altium Limited")
      )
      (libsource (lib "HabLib") (part "CDERA00170"))
    )
    (comp (ref "R30")
      (value "10K")
      (footprint "HabLib:3216[1206]")
      (description "RESISTOR, CHIP 1206 10K OHM 1% 1/4W THICK FILM ROHS")
      (fields
        (field (name "MFG") "PANASONIC")
        (field (name "TOLERANCE") "1%")
        (field (name "POWER") ".25W")
        (field (name "Comment") "CDERA00170")
        (field (name "PUBLISHER") "Altium Limited")
      )
      (libsource (lib "HabLib") (part "CDERA00170"))
    )
    (comp (ref "R31")
      (value "100")
      (footprint "HabLib:3216[1206]")
      (description "RESISTOR, CHIP 1206 100 OHM 1% 1/4W THICK FILM ROHS")
      (fields
        (field (name "MFG") "PANASONIC")
        (field (name "TOLERANCE") "1%")
        (field (name "POWER") ".25W")
        (field (name "Comment") "CDERA00176")
        (field (name "PUBLISHER") "Altium Limited")
      )
      (libsource (lib "HabLib") (part "CDERA00176"))
    )
    (comp (ref "R32")
      (value "330")
      (footprint "HABLIB:3216[1206]")
      (description "RESISTOR, CHIP 1206 330 OHM 1% 1/4W THICK FILM ROHS")
      (fields
        (field (name "MFG") "PANASONIC")
        (field (name "TOLERANCE") "1%")
        (field (name "POWER") ".25W")
        (field (name "Comment") "CDERA00154")
        (field (name "PUBLISHER") "Altium Limited")
      )
      (libsource (lib "HabLib") (part "CDERA00154"))
    )
    (comp (ref "R33")
      (value "100K")
      (footprint "HABLIB:3216[1206]")
      (description "RESISTOR, CHIP 1206 100K OHM 1% 1/4W THICK FILM ROHS")
      (fields
        (field (name "MFG") "PANASONIC")
        (field (name "TOLERANCE") "1%")
        (field (name "POWER") ".25W")
        (field (name "Comment") "CDERA00198")
        (field (name "PUBLISHER") "Altium Limited")
      )
      (libsource (lib "HabLib") (part "CDERA00198"))
    )
    (comp (ref "R34")
      (value "300K")
      (footprint "HABLIB:3216[1206]")
      (description "RESISTOR, CHIP 1206 300K OHM 1% 1/4W THICK FILM ROHS")
      (fields
        (field (name "MFG") "PANASONIC")
        (field (name "TOLERANCE") "1%")
        (field (name "POWER") ".25W")
        (field (name "Comment") "CDERA00275_8")
        (field (name "PUBLISHER") "Altium Limited")
      )
      (libsource (lib "HabLib") (part "CDERA00275_8"))
    )
    (comp (ref "R35")
      (value "10K")
      (footprint "HabLib:3216[1206]")
      (description "RESISTOR, CHIP 1206 10K OHM 1% 1/4W THICK FILM ROHS")
      (fields
        (field (name "MFG") "PANASONIC")
        (field (name "TOLERANCE") "1%")
        (field (name "POWER") ".25W")
        (field (name "Comment") "CDERA00170")
        (field (name "PUBLISHER") "Altium Limited")
      )
      (libsource (lib "HabLib") (part "CDERA00170"))
    )
    (comp (ref "R36")
      (value "300K")
      (footprint "HABLIB:3216[1206]")
      (description "RESISTOR, CHIP 1206 300K OHM 1% 1/4W THICK FILM ROHS")
      (fields
        (field (name "MFG") "PANASONIC")
        (field (name "TOLERANCE") "1%")
        (field (name "POWER") ".25W")
        (field (name "Comment") "CDERA00275_8")
        (field (name "PUBLISHER") "Altium Limited")
      )
      (libsource (lib "HabLib") (part "CDERA00275_8"))
    )
    (comp (ref "R37")
      (value "100K")
      (footprint "HABLIB:3216[1206]")
      (description "RESISTOR, CHIP 1206 100K OHM 1% 1/4W THICK FILM ROHS")
      (fields
        (field (name "MFG") "PANASONIC")
        (field (name "TOLERANCE") "1%")
        (field (name "POWER") ".25W")
        (field (name "Comment") "CDERA00198")
        (field (name "PUBLISHER") "Altium Limited")
      )
      (libsource (lib "HabLib") (part "CDERA00198"))
    )
    (comp (ref "R38")
      (value "220")
      (footprint "HABLIB:3216[1206]")
      (description "RESISTOR, CHIP 1206 220 OHM 1% 1/4W THICK FILM ROHS")
      (fields
        (field (name "MFG") "PANASONIC")
        (field (name "TOLERANCE") "1%")
        (field (name "POWER") ".25W")
        (field (name "Comment") "CDERA00273_2")
        (field (name "PUBLISHER") "Altium Limited")
      )
      (libsource (lib "HabLib") (part "CDERA00273_2"))
    )
    (comp (ref "R39")
      (value "100K")
      (footprint "HABLIB:3216[1206]")
      (description "RESISTOR, CHIP 1206 100K OHM 1% 1/4W THICK FILM ROHS")
      (fields
        (field (name "MFG") "PANASONIC")
        (field (name "TOLERANCE") "1%")
        (field (name "POWER") ".25W")
        (field (name "Comment") "CDERA00198")
        (field (name "PUBLISHER") "Altium Limited")
      )
      (libsource (lib "HabLib") (part "CDERA00198"))
    )
    (comp (ref "R40")
      (value "3.32K")
      (footprint "HABLIB:3216[1206]")
      (description "RESISTOR, CHIP 1206 3.32K OHM 1% 1/4W THICK FILM ROHS")
      (fields
        (field (name "MFG") "PANASONIC")
        (field (name "TOLERANCE") "1%")
        (field (name "POWER") ".25W")
        (field (name "Comment") "CDERA00273_1")
        (field (name "PUBLISHER") "Altium Limited")
      )
      (libsource (lib "HabLib") (part "CDERA00273_1"))
    )
    (comp (ref "R41")
      (value "11K")
      (footprint "HABLIB:3216[1206]")
      (description "RESISTOR, CHIP 1206 11K OHM 1% 1/4W THICK FILM ROHS")
      (fields
        (field (name "MFG") "PANASONIC")
        (field (name "TOLERANCE") "1%")
        (field (name "POWER") ".25W")
        (field (name "Comment") "CDERA00275_2")
        (field (name "PUBLISHER") "Altium Limited")
      )
      (libsource (lib "HabLib") (part "CDERA00275_2"))
    )
    (comp (ref "R42")
      (value "59K")
      (footprint "HABLIB:3216[1206]")
      (description "RESISTOR, CHIP 1206 59K OHM 1% 1/4W THICK FILM ROHS")
      (fields
        (field (name "MFG") "PANASONIC")
        (field (name "TOLERANCE") "1%")
        (field (name "POWER") ".25W")
        (field (name "Comment") "CDERA00275_7")
        (field (name "PUBLISHER") "Altium Limited")
      )
      (libsource (lib "HabLib") (part "CDERA00275_7"))
    )
    (comp (ref "R43")
      (value "100K")
      (footprint "HABLIB:3216[1206]")
      (description "RESISTOR, CHIP 1206 100K OHM 1% 1/4W THICK FILM ROHS")
      (fields
        (field (name "MFG") "PANASONIC")
        (field (name "TOLERANCE") "1%")
        (field (name "POWER") ".25W")
        (field (name "Comment") "CDERA00198")
        (field (name "PUBLISHER") "Altium Limited")
      )
      (libsource (lib "HabLib") (part "CDERA00198"))
    )
    (comp (ref "R44")
      (value "300K")
      (footprint "HABLIB:3216[1206]")
      (description "RESISTOR, CHIP 1206 300K OHM 1% 1/4W THICK FILM ROHS")
      (fields
        (field (name "MFG") "PANASONIC")
        (field (name "TOLERANCE") "1%")
        (field (name "POWER") ".25W")
        (field (name "Comment") "CDERA00275_8")
        (field (name "PUBLISHER") "Altium Limited")
      )
      (libsource (lib "HabLib") (part "CDERA00275_8"))
    )
    (comp (ref "R45")
      (value "180")
      (footprint "HABLIB:3216[1206]")
      (description "RESISTOR, CHIP 1206 180 OHM 1% 1/4W THICK FILM ROHS")
      (fields
        (field (name "MFG") "PANASONIC")
        (field (name "TOLERANCE") "1%")
        (field (name "POWER") ".25W")
        (field (name "Comment") "CDERA00192")
        (field (name "PUBLISHER") "Altium Limited")
      )
      (libsource (lib "HabLib") (part "CDERA00192"))
    )
    (comp (ref "R46")
      (value "1K")
      (footprint "HABLIB:3216[1206]")
      (description "RESISTOR, CHIP 1206 1K OHM 1% 1/4W THICK FILM ROHS")
      (fields
        (field (name "MFG") "PANASONIC")
        (field (name "TOLERANCE") "1%")
        (field (name "POWER") ".25W")
        (field (name "Comment") "CDERA00195")
        (field (name "PUBLISHER") "Altium Limited")
      )
      (libsource (lib "HabLib") (part "CDERA00195"))
    )
    (comp (ref "R47")
      (value "30K")
      (footprint "HABLIB:3216[1206]")
      (description "RESISTOR, CHIP 1206 30K OHM 1% 1/4W THICK FILM ROHS")
      (fields
        (field (name "MFG") "PANASONIC")
        (field (name "TOLERANCE") "1%")
        (field (name "POWER") ".25W")
        (field (name "Comment") "CDERA00275_4")
        (field (name "PUBLISHER") "Altium Limited")
      )
      (libsource (lib "HabLib") (part "CDERA00275_4"))
    )
    (comp (ref "R48")
      (value "12K")
      (footprint "HABLIB:3216[1206]")
      (description "RESISTOR, CHIP 1206 12K OHM 1% 1/4W THICK FILM ROHS")
      (fields
        (field (name "MFG") "PANASONIC")
        (field (name "TOLERANCE") "1%")
        (field (name "POWER") ".25W")
        (field (name "Comment") "CDERA00275_5")
        (field (name "PUBLISHER") "Altium Limited")
      )
      (libsource (lib "HabLib") (part "CDERA00275_5"))
    )
    (comp (ref "R49")
      (value "7.5K")
      (footprint "HABLIB:3216[1206]")
      (description "RESISTOR, CHIP 1206 7.5K OHM 1% 1/4W THICK FILM ROHS")
      (fields
        (field (name "MFG") "PANASONIC")
        (field (name "TOLERANCE") "1%")
        (field (name "POWER") ".25W")
        (field (name "Comment") "CDERA00275_3")
        (field (name "PUBLISHER") "Altium Limited")
      )
      (libsource (lib "HabLib") (part "CDERA00275_3"))
    )
    (comp (ref "R50")
      (value "0")
      (footprint "HABLIB:3216[1206]")
      (description "RESISTOR, CHIP 1206 0.0 OHM 1% 1/4W THICK FILM ROHS")
      (fields
        (field (name "MFG") "PANASONIC")
        (field (name "TOLERANCE") "1%")
        (field (name "POWER") ".25W")
        (field (name "Comment") "CDERA00181")
        (field (name "PUBLISHER") "Altium Limited")
      )
      (libsource (lib "HabLib") (part "CDERA00181"))
    )
    (comp (ref "R51")
      (value "0")
      (footprint "HABLIB:3216[1206]")
      (description "RESISTOR, CHIP 1206 0.0 OHM 1% 1/4W THICK FILM ROHS")
      (fields
        (field (name "MFG") "PANASONIC")
        (field (name "TOLERANCE") "1%")
        (field (name "POWER") ".25W")
        (field (name "Comment") "CDERA00181")
        (field (name "PUBLISHER") "Altium Limited")
      )
      (libsource (lib "HabLib") (part "CDERA00181"))
    )
    (comp (ref "R52")
      (value "357")
      (footprint "HABLIB:3216[1206]")
      (description "RESISTOR, CHIP 1206 357 OHM 1% 1/4W THICK FILM ROHS")
      (fields
        (field (name "MFG") "PANASONIC")
        (field (name "TOLERANCE") "1%")
        (field (name "POWER") ".25W")
        (field (name "Comment") "CDERA00275_6")
        (field (name "PUBLISHER") "Altium Limited")
      )
      (libsource (lib "HabLib") (part "CDERA00275_6"))
    )
    (comp (ref "R53")
      (value "270")
      (footprint "HABLIB:3216[1206]")
      (description "RESISTOR, CHIP 1206 270 OHM 1% 1/4W THICK FILM ROHS")
      (fields
        (field (name "MFG") "PANASONIC")
        (field (name "TOLERANCE") "1%")
        (field (name "POWER") ".25W")
        (field (name "Comment") "CDERA00209")
        (field (name "PUBLISHER") "Altium Limited")
      )
      (libsource (lib "HabLib") (part "CDERA00209"))
    )
    (comp (ref "R54")
      (value "100K")
      (footprint "HABLIB:3216[1206]")
      (description "RESISTOR, CHIP 1206 100K OHM 1% 1/4W THICK FILM ROHS")
      (fields
        (field (name "MFG") "PANASONIC")
        (field (name "TOLERANCE") "1%")
        (field (name "POWER") ".25W")
        (field (name "Comment") "CDERA00198")
        (field (name "PUBLISHER") "Altium Limited")
      )
      (libsource (lib "HabLib") (part "CDERA00198"))
    )
    (comp (ref "R55")
      (value "1K")
      (footprint "HABLIB:3216[1206]")
      (description "RESISTOR, CHIP 1206 1K OHM 1% 1/4W THICK FILM ROHS")
      (fields
        (field (name "MFG") "PANASONIC")
        (field (name "TOLERANCE") "1%")
        (field (name "POWER") ".25W")
        (field (name "Comment") "CDERA00195")
        (field (name "PUBLISHER") "Altium Limited")
      )
      (libsource (lib "HabLib") (part "CDERA00195"))
    )
    (comp (ref "R56")
      (value "100K")
      (footprint "HABLIB:3216[1206]")
      (description "RESISTOR, CHIP 1206 100K OHM 1% 1/4W THICK FILM ROHS")
      (fields
        (field (name "MFG") "PANASONIC")
        (field (name "TOLERANCE") "1%")
        (field (name "POWER") ".25W")
        (field (name "Comment") "CDERA00198")
        (field (name "PUBLISHER") "Altium Limited")
      )
      (libsource (lib "HabLib") (part "CDERA00198"))
    )
    (comp (ref "U7")
      (value "STMPE24M31")
      (footprint "QFN40P500X500X80-41V_MODIFIED")
      (description "IC, TOUCHKEY CONTROLLER, 24CH, I2C, 40QFN")
      (fields
        (field (name "MFG") "ST")
        (field (name "Comment") "CDEUA00052_1")
        (field (name "PUBLISHER") "Altium Limited")
      )
      (libsource (lib "HabLib") (part "CDEUA00052_1"))
    )
    (comp (ref "U8")
      (value "STMPE24M31")
      (footprint "QFN40P500X500X80-41V_MODIFIED")
      (description "IC, TOUCHKEY CONTROLLER, 24CH, I2C, 40QFN")
      (fields
        (field (name "MFG") "ST")
        (field (name "Comment") "CDEUA00052_1")
        (field (name "PUBLISHER") "Altium Limited")
      )
      (libsource (lib "HabLib") (part "CDEUA00052_1"))
    )
    (comp (ref "U9")
      (value "LM2842X")
      (footprint "TSOT6")
      (description "IC, BUCK REGULATOR, 0.6A, TSOT23-6")
      (fields (field (name "MFG") "NATIONAL SEMICONDUCTOR") (field (name "Comment") "CDEUA00014_1"))
      (libsource (lib "HabLib") (part "CDEUA00014_1"))
    )
    (comp (ref "U10")
      (value "PC817X2NIP0F")
      (footprint "SHARP_PC817")
      (description "IC, PHOTOCOUPLER, NPN OUTPUT - NO BASE, SM, ROHS")
      (fields (field (name "MFG") "SHARP MICROELECTRONICS") (field (name "Comment") "CDEUA00013_1"))
      (libsource (lib "HabLib") (part "CDEUA00013_1"))
    )
  )
  (nets
    (net (code "1") (name "/ACAP0") (class "Default")
      (node (ref "CS37") (pin "1") (pinfunction "1_1") (pintype "passive"))
      (node (ref "U7") (pin "1") (pinfunction "CAP0_1") (pintype "passive"))
    )
    (net (code "2") (name "/ACAP1") (class "Default")
      (node (ref "CS27") (pin "1") (pinfunction "1_1") (pintype "passive"))
      (node (ref "U7") (pin "2") (pinfunction "CAP1_2") (pintype "passive"))
    )
    (net (code "3") (name "/ACAP2") (class "Default")
      (node (ref "CS26") (pin "1") (pinfunction "1_1") (pintype "passive"))
      (node (ref "U7") (pin "3") (pinfunction "CAP2_3") (pintype "passive"))
    )
    (net (code "4") (name "/ACAP3") (class "Default")
      (node (ref "CS14") (pin "1") (pinfunction "1_1") (pintype "passive"))
      (node (ref "U7") (pin "8") (pinfunction "CAP3_8") (pintype "passive"))
    )
    (net (code "5") (name "/ACAP4") (class "Default")
      (node (ref "CS15") (pin "1") (pinfunction "1_1") (pintype "passive"))
      (node (ref "U7") (pin "9") (pinfunction "CAP4_9") (pintype "passive"))
    )
    (net (code "6") (name "/ACAP5") (class "Default")
      (node (ref "CS1") (pin "1") (pinfunction "1_1") (pintype "passive"))
      (node (ref "U7") (pin "10") (pinfunction "CAP5_10") (pintype "passive"))
    )
    (net (code "7") (name "/ACAP6") (class "Default")
      (node (ref "CS2") (pin "1") (pinfunction "1_1") (pintype "passive"))
      (node (ref "U7") (pin "11") (pinfunction "CAP6_11") (pintype "passive"))
    )
    (net (code "8") (name "/ACAP7") (class "Default")
      (node (ref "CS3") (pin "1") (pinfunction "1_1") (pintype "passive"))
      (node (ref "U7") (pin "12") (pinfunction "CAP7_12") (pintype "passive"))
    )
    (net (code "9") (name "/ACAP8") (class "Default")
      (node (ref "CS17") (pin "1") (pinfunction "1_1") (pintype "passive"))
      (node (ref "U7") (pin "28") (pinfunction "CAP8_28") (pintype "passive"))
    )
    (net (code "10") (name "/ACAP9") (class "Default")
      (node (ref "CS18") (pin "1") (pinfunction "1_1") (pintype "passive"))
      (node (ref "U7") (pin "29") (pinfunction "CAP9_29") (pintype "passive"))
    )
    (net (code "11") (name "/ACAP10") (class "Default")
      (node (ref "CS30") (pin "1") (pinfunction "1_1") (pintype "passive"))
      (node (ref "U7") (pin "31") (pinfunction "CAP10_31") (pintype "passive"))
    )
    (net (code "12") (name "/ACAP11") (class "Default")
      (node (ref "CS29") (pin "1") (pinfunction "1_1") (pintype "passive"))
      (node (ref "U7") (pin "32") (pinfunction "CAP11_32") (pintype "passive"))
    )
    (net (code "13") (name "/ACAP12") (class "Default")
      (node (ref "CS28") (pin "1") (pinfunction "1_1") (pintype "passive"))
      (node (ref "U7") (pin "33") (pinfunction "CAP12_33") (pintype "passive"))
    )
    (net (code "14") (name "/ACAP13") (class "Default")
      (node (ref "CS42") (pin "1") (pinfunction "1_1") (pintype "passive"))
      (node (ref "U7") (pin "34") (pinfunction "CAP13_34") (pintype "passive"))
    )
    (net (code "15") (name "/ACAP14") (class "Default")
      (node (ref "CS39") (pin "1") (pinfunction "1_1") (pintype "passive"))
      (node (ref "U7") (pin "39") (pinfunction "CAP14_39") (pintype "passive"))
    )
    (net (code "16") (name "/ACAP15") (class "Default")
      (node (ref "CS38") (pin "1") (pinfunction "1_1") (pintype "passive"))
      (node (ref "U7") (pin "40") (pinfunction "CAP15_40") (pintype "passive"))
    )
    (net (code "17") (name "/ACAP16") (class "Default")
      (node (ref "CS25") (pin "1") (pinfunction "1_1") (pintype "passive"))
      (node (ref "U7") (pin "6") (pinfunction "CAP16_6") (pintype "passive"))
    )
    (net (code "18") (name "/ACAP17") (class "Default")
      (node (ref "CS13") (pin "1") (pinfunction "1_1") (pintype "passive"))
      (node (ref "U7") (pin "7") (pinfunction "CAP17_7") (pintype "passive"))
    )
    (net (code "19") (name "/ACAP18") (class "Default")
      (node (ref "CS4") (pin "1") (pinfunction "1_1") (pintype "passive"))
      (node (ref "U7") (pin "15") (pinfunction "CAP18_15") (pintype "passive"))
    )
    (net (code "20") (name "/ACAP19") (class "Default")
      (node (ref "CS5") (pin "1") (pinfunction "1_1") (pintype "passive"))
      (node (ref "U7") (pin "16") (pinfunction "CAP19_16") (pintype "passive"))
    )
    (net (code "21") (name "/ACAP20") (class "Default")
      (node (ref "CS6") (pin "1") (pinfunction "1_1") (pintype "passive"))
      (node (ref "U7") (pin "25") (pinfunction "CAP20_25") (pintype "passive"))
    )
    (net (code "22") (name "/ACAP21") (class "Default")
      (node (ref "CS16") (pin "1") (pinfunction "1_1") (pintype "passive"))
      (node (ref "U7") (pin "26") (pinfunction "CAP21_26") (pintype "passive"))
    )
    (net (code "23") (name "/ACAP22") (class "Default")
      (node (ref "CS41") (pin "1") (pinfunction "1_1") (pintype "passive"))
      (node (ref "U7") (pin "37") (pinfunction "CPA22_37") (pintype "passive"))
    )
    (net (code "24") (name "/ACAP23") (class "Default")
      (node (ref "CS40") (pin "1") (pinfunction "1_1") (pintype "passive"))
      (node (ref "U7") (pin "38") (pinfunction "CAP23_38") (pintype "passive"))
    )
    (net (code "25") (name "/ADC_BAT") (class "Default")
      (node (ref "C40") (pin "1") (pinfunction "1_1") (pintype "passive"))
      (node (ref "R37") (pin "1") (pinfunction "1_1") (pintype "passive"))
      (node (ref "R39") (pin "2") (pinfunction "2_2") (pintype "passive"))
    )
    (net (code "26") (name "/ADC_METER") (class "Default")
      (node (ref "C44") (pin "1") (pinfunction "1_1") (pintype "passive"))
      (node (ref "D19") (pin "1") (pinfunction "A_1") (pintype "passive"))
      (node (ref "D21") (pin "2") (pinfunction "K_2") (pintype "passive"))
      (node (ref "R31") (pin "2") (pinfunction "2_2") (pintype "passive"))
      (node (ref "R42") (pin "2") (pinfunction "2_2") (pintype "passive"))
      (node (ref "R47") (pin "2") (pinfunction "2_2") (pintype "passive"))
      (node (ref "R48") (pin "2") (pinfunction "2_2") (pintype "passive"))
      (node (ref "R49") (pin "2") (pinfunction "2_2") (pintype "passive"))
    )
    (net (code "27") (name "/BCAP0") (class "Default")
      (node (ref "CS34") (pin "1") (pinfunction "1_1") (pintype "passive"))
      (node (ref "U8") (pin "1") (pinfunction "CAP0_1") (pintype "passive"))
    )
    (net (code "28") (name "/BCAP1") (class "Default")
      (node (ref "CS35") (pin "1") (pinfunction "1_1") (pintype "passive"))
      (node (ref "U8") (pin "2") (pinfunction "CAP1_2") (pintype "passive"))
    )
    (net (code "29") (name "/BCAP2") (class "Default")
      (node (ref "CS47") (pin "1") (pinfunction "1_1") (pintype "passive"))
      (node (ref "U8") (pin "3") (pinfunction "CAP2_3") (pintype "passive"))
    )
    (net (code "30") (name "/BCAP3") (class "Default")
      (node (ref "CS44") (pin "1") (pinfunction "1_1") (pintype "passive"))
      (node (ref "U8") (pin "8") (pinfunction "CAP3_8") (pintype "passive"))
    )
    (net (code "31") (name "/BCAP4") (class "Default")
      (node (ref "CS32") (pin "1") (pinfunction "1_1") (pintype "passive"))
      (node (ref "U8") (pin "9") (pinfunction "CAP4_9") (pintype "passive"))
    )
    (net (code "32") (name "/BCAP5") (class "Default")
      (node (ref "CS43") (pin "1") (pinfunction "1_1") (pintype "passive"))
      (node (ref "U8") (pin "10") (pinfunction "CAP5_10") (pintype "passive"))
    )
    (net (code "33") (name "/BCAP6") (class "Default")
      (node (ref "CS19") (pin "1") (pinfunction "1_1") (pintype "passive"))
      (node (ref "U8") (pin "11") (pinfunction "CAP6_11") (pintype "passive"))
    )
    (net (code "34") (name "/BCAP7") (class "Default")
      (node (ref "CS20") (pin "1") (pinfunction "1_1") (pintype "passive"))
      (node (ref "U8") (pin "12") (pinfunction "CAP7_12") (pintype "passive"))
    )
    (net (code "35") (name "/BCAP8") (class "Default")
      (node (ref "CS31") (pin "1") (pinfunction "1_1") (pintype "passive"))
      (node (ref "U8") (pin "28") (pinfunction "CAP8_28") (pintype "passive"))
    )
    (net (code "36") (name "/BCAP9") (class "Default")
      (node (ref "CS36") (pin "1") (pinfunction "1_1") (pintype "passive"))
      (node (ref "U8") (pin "29") (pinfunction "CAP9_29") (pintype "passive"))
    )
    (net (code "37") (name "/BCAP10") (class "Default")
      (node (ref "CS48") (pin "1") (pinfunction "1_1") (pintype "passive"))
      (node (ref "U8") (pin "31") (pinfunction "CAP10_31") (pintype "passive"))
    )
    (net (code "38") (name "/BCAP11") (class "Default")
      (node (ref "CS9") (pin "1") (pinfunction "1_1") (pintype "passive"))
      (node (ref "U8") (pin "32") (pinfunction "CAP11_32") (pintype "passive"))
    )
    (net (code "39") (name "/BCAP12") (class "Default")
      (node (ref "CS10") (pin "1") (pinfunction "1_1") (pintype "passive"))
      (node (ref "U8") (pin "33") (pinfunction "CAP12_33") (pintype "passive"))
    )
    (net (code "40") (name "/BCAP13") (class "Default")
      (node (ref "CS11") (pin "1") (pinfunction "1_1") (pintype "passive"))
      (node (ref "U8") (pin "34") (pinfunction "CAP13_34") (pintype "passive"))
    )
    (net (code "41") (name "/BCAP14") (class "Default")
      (node (ref "CS23") (pin "1") (pinfunction "1_1") (pintype "passive"))
      (node (ref "U8") (pin "39") (pinfunction "CAP14_39") (pintype "passive"))
    )
    (net (code "42") (name "/BCAP15") (class "Default")
      (node (ref "CS33") (pin "1") (pinfunction "1_1") (pintype "passive"))
      (node (ref "U8") (pin "40") (pinfunction "CAP15_40") (pintype "passive"))
    )
    (net (code "43") (name "/BCAP16") (class "Default")
      (node (ref "CS46") (pin "1") (pinfunction "1_1") (pintype "passive"))
      (node (ref "U8") (pin "6") (pinfunction "CAP16_6") (pintype "passive"))
    )
    (net (code "44") (name "/BCAP17") (class "Default")
      (node (ref "CS45") (pin "1") (pinfunction "1_1") (pintype "passive"))
      (node (ref "U8") (pin "7") (pinfunction "CAP17_7") (pintype "passive"))
    )
    (net (code "45") (name "/BCAP18") (class "Default")
      (node (ref "CS7") (pin "1") (pinfunction "1_1") (pintype "passive"))
      (node (ref "U8") (pin "15") (pinfunction "CAP18_15") (pintype "passive"))
    )
    (net (code "46") (name "/BCAP19") (class "Default")
      (node (ref "CS8") (pin "1") (pinfunction "1_1") (pintype "passive"))
      (node (ref "U8") (pin "16") (pinfunction "CAP19_16") (pintype "passive"))
    )
    (net (code "47") (name "/BCAP20") (class "Default")
      (node (ref "CS12") (pin "1") (pinfunction "1_1") (pintype "passive"))
      (node (ref "U8") (pin "25") (pinfunction "CAP20_25") (pintype "passive"))
    )
    (net (code "48") (name "/BCAP21") (class "Default")
      (node (ref "CS24") (pin "1") (pinfunction "1_1") (pintype "passive"))
      (node (ref "U8") (pin "26") (pinfunction "CAP21_26") (pintype "passive"))
    )
    (net (code "49") (name "/BCAP22") (class "Default")
      (node (ref "CS21") (pin "1") (pinfunction "1_1") (pintype "passive"))
      (node (ref "U8") (pin "37") (pinfunction "CPA22_37") (pintype "passive"))
    )
    (net (code "50") (name "/BCAP23") (class "Default")
      (node (ref "CS22") (pin "1") (pinfunction "1_1") (pintype "passive"))
      (node (ref "U8") (pin "38") (pinfunction "CAP23_38") (pintype "passive"))
    )
    (net (code "51") (name "/INT_ACAP") (class "Default")
      (node (ref "R29") (pin "1") (pinfunction "1_1") (pintype "passive"))
      (node (ref "U7") (pin "18") (pinfunction "INT_18") (pintype "passive"))
    )
    (net (code "52") (name "/INT_BCAP") (class "Default")
      (node (ref "R30") (pin "1") (pinfunction "1_1") (pintype "passive"))
      (node (ref "U8") (pin "18") (pinfunction "INT_18") (pintype "passive"))
    )
    (net (code "53") (name "/PWM_BL") (class "Default")
      (node (ref "Q6") (pin "1") (pinfunction "B_1") (pintype "passive"))
    )
    (net (code "54") (name "/RNG_10") (class "Default")
      (node (ref "Q11") (pin "1") (pinfunction "B_1") (pintype "passive"))
    )
    (net (code "55") (name "/RNG_20") (class "Default")
      (node (ref "Q12") (pin "1") (pinfunction "B_1") (pintype "passive"))
    )
    (net (code "56") (name "/RNG_30") (class "Default")
      (node (ref "Q13") (pin "1") (pinfunction "B_1") (pintype "passive"))
    )
    (net (code "57") (name "/SCL0") (class "Default")
      (node (ref "U7") (pin "20") (pinfunction "SCL_20") (pintype "passive"))
      (node (ref "U8") (pin "20") (pinfunction "SCL_20") (pintype "passive"))
    )
    (net (code "58") (name "/SDA0") (class "Default")
      (node (ref "U7") (pin "21") (pinfunction "SDA_21") (pintype "passive"))
      (node (ref "U8") (pin "21") (pinfunction "SDA_21") (pintype "passive"))
    )
    (net (code "59") (name "/SEL_V{slash}~{C}") (class "Default")
      (node (ref "Q16") (pin "1") (pinfunction "B_1") (pintype "passive"))
      (node (ref "Q8") (pin "1") (pinfunction "B_1") (pintype "passive"))
      (node (ref "R56") (pin "1") (pinfunction "1_1") (pintype "passive"))
    )
    (net (code "60") (name "/SYS_RST") (class "Default")
      (node (ref "U7") (pin "22") (pinfunction "RST_22") (pintype "passive"))
      (node (ref "U8") (pin "22") (pinfunction "RST_22") (pintype "passive"))
    )
    (net (code "61") (name "/VREF30") (class "Default")
      (node (ref "Q10") (pin "2") (pinfunction "E_2") (pintype "passive"))
      (node (ref "R54") (pin "2") (pinfunction "2_2") (pintype "passive"))
    )
    (net (code "62") (name "3.3V") (class "Default")
      (node (ref "C29") (pin "1") (pinfunction "1_1") (pintype "passive"))
      (node (ref "C30") (pin "1") (pinfunction "1_1") (pintype "passive"))
      (node (ref "C31") (pin "1") (pinfunction "1_1") (pintype "passive"))
      (node (ref "C32") (pin "1") (pinfunction "1_1") (pintype "passive"))
      (node (ref "C33") (pin "1") (pinfunction "1_1") (pintype "passive"))
      (node (ref "C34") (pin "1") (pinfunction "1_1") (pintype "passive"))
      (node (ref "C35") (pin "1") (pinfunction "1_1") (pintype "passive"))
      (node (ref "C36") (pin "1") (pinfunction "1_1") (pintype "passive"))
      (node (ref "C38") (pin "1") (pinfunction "1_1") (pintype "passive"))
      (node (ref "C39") (pin "1") (pinfunction "1_1") (pintype "passive"))
      (node (ref "D19") (pin "2") (pinfunction "K_2") (pintype "passive"))
      (node (ref "L1") (pin "2") (pinfunction "2_2") (pintype "passive"))
      (node (ref "R29") (pin "2") (pinfunction "2_2") (pintype "passive"))
      (node (ref "R30") (pin "2") (pinfunction "2_2") (pintype "passive"))
      (node (ref "R33") (pin "2") (pinfunction "2_2") (pintype "passive"))
      (node (ref "R40") (pin "2") (pinfunction "2_2") (pintype "passive"))
      (node (ref "R56") (pin "2") (pinfunction "2_2") (pintype "passive"))
      (node (ref "U7") (pin "14") (pinfunction "VIO_14") (pintype "passive"))
      (node (ref "U7") (pin "30") (pinfunction "VIO_30") (pintype "passive"))
      (node (ref "U7") (pin "35") (pinfunction "VIO_35") (pintype "passive"))
      (node (ref "U7") (pin "5") (pinfunction "VIO_5") (pintype "passive"))
      (node (ref "U8") (pin "14") (pinfunction "VIO_14") (pintype "passive"))
      (node (ref "U8") (pin "19") (pinfunction "ADDR0_19") (pintype "passive"))
      (node (ref "U8") (pin "30") (pinfunction "VIO_30") (pintype "passive"))
      (node (ref "U8") (pin "35") (pinfunction "VIO_35") (pintype "passive"))
      (node (ref "U8") (pin "5") (pinfunction "VIO_5") (pintype "passive"))
    )
    (net (code "63") (name "6V") (class "Default")
      (node (ref "BAT1") (pin "1") (pinfunction "1_1") (pintype "passive"))
      (node (ref "Q4") (pin "2") (pinfunction "E_2") (pintype "passive"))
      (node (ref "R32") (pin "2") (pinfunction "2_2") (pintype "passive"))
      (node (ref "R37") (pin "2") (pinfunction "2_2") (pintype "passive"))
      (node (ref "R43") (pin "2") (pinfunction "2_2") (pintype "passive"))
      (node (ref "R44") (pin "2") (pinfunction "2_2") (pintype "passive"))
    )
    (net (code "64") (name "GND") (class "Default")
      (node (ref "BAT1") (pin "2") (pinfunction "2_2") (pintype "passive"))
      (node (ref "C25") (pin "2") (pinfunction "2_2") (pintype "passive"))
      (node (ref "C26") (pin "2") (pinfunction "2_2") (pintype "passive"))
      (node (ref "C27") (pin "2") (pinfunction "2_2") (pintype "passive"))
      (node (ref "C28") (pin "2") (pinfunction "2_2") (pintype "passive"))
      (node (ref "C29") (pin "2") (pinfunction "2_2") (pintype "passive"))
      (node (ref "C30") (pin "2") (pinfunction "2_2") (pintype "passive"))
      (node (ref "C31") (pin "2") (pinfunction "2_2") (pintype "passive"))
      (node (ref "C32") (pin "2") (pinfunction "2_2") (pintype "passive"))
      (node (ref "C33") (pin "2") (pinfunction "2_2") (pintype "passive"))
      (node (ref "C34") (pin "2") (pinfunction "2_2") (pintype "passive"))
      (node (ref "C35") (pin "2") (pinfunction "2_2") (pintype "passive"))
      (node (ref "C36") (pin "2") (pinfunction "2_2") (pintype "passive"))
      (node (ref "C38") (pin "2") (pinfunction "2_2") (pintype "passive"))
      (node (ref "C39") (pin "2") (pinfunction "2_2") (pintype "passive"))
      (node (ref "C40") (pin "2") (pinfunction "2_2") (pintype "passive"))
      (node (ref "C41") (pin "1") (pinfunction "1_1") (pintype "passive"))
      (node (ref "C42") (pin "2") (pinfunction "2_2") (pintype "passive"))
      (node (ref "C43") (pin "2") (pinfunction "2_2") (pintype "passive"))
      (node (ref "C46") (pin "2") (pinfunction "2_2") (pintype "passive"))
      (node (ref "D18") (pin "1") (pinfunction "A_1") (pintype "passive"))
      (node (ref "FB5") (pin "1") (pinfunction "1_1") (pintype "passive"))
      (node (ref "Q6") (pin "2") (pinfunction "E_2") (pintype "passive"))
      (node (ref "Q9") (pin "2") (pinfunction "E_2") (pintype "passive"))
      (node (ref "R39") (pin "1") (pinfunction "1_1") (pintype "passive"))
      (node (ref "R46") (pin "1") (pinfunction "1_1") (pintype "passive"))
      (node (ref "U10") (pin "2") (pintype "passive"))
      (node (ref "U10") (pin "3") (pintype "passive"))
      (node (ref "U7") (pin "13") (pinfunction "GND_13") (pintype "passive"))
      (node (ref "U7") (pin "19") (pinfunction "ADDR0_19") (pintype "passive"))
      (node (ref "U7") (pin "23") (pinfunction "ADDR1_23") (pintype "passive"))
      (node (ref "U7") (pin "27") (pinfunction "GND_27") (pintype "passive"))
      (node (ref "U7") (pin "36") (pinfunction "GND_36") (pintype "passive"))
      (node (ref "U7") (pin "4") (pinfunction "GND_4") (pintype "passive"))
      (node (ref "U8") (pin "13") (pinfunction "GND_13") (pintype "passive"))
      (node (ref "U8") (pin "23") (pinfunction "ADDR1_23") (pintype "passive"))
      (node (ref "U8") (pin "27") (pinfunction "GND_27") (pintype "passive"))
      (node (ref "U8") (pin "36") (pinfunction "GND_36") (pintype "passive"))
      (node (ref "U8") (pin "4") (pinfunction "GND_4") (pintype "passive"))
      (node (ref "U9") (pin "2") (pinfunction "GND_2") (pintype "passive"))
    )
    (net (code "65") (name "GNDA") (class "Default")
      (node (ref "C44") (pin "2") (pinfunction "2_2") (pintype "passive"))
      (node (ref "D21") (pin "1") (pinfunction "A_1") (pintype "passive"))
      (node (ref "FB5") (pin "2") (pinfunction "2_2") (pintype "passive"))
      (node (ref "Q11") (pin "2") (pinfunction "E_2") (pintype "passive"))
      (node (ref "Q12") (pin "2") (pinfunction "E_2") (pintype "passive"))
      (node (ref "Q13") (pin "2") (pinfunction "E_2") (pintype "passive"))
      (node (ref "Q15") (pin "2") (pinfunction "E_2") (pintype "passive"))
      (node (ref "Q16") (pin "2") (pinfunction "E_2") (pintype "passive"))
      (node (ref "Q7") (pin "2") (pinfunction "E_2") (pintype "passive"))
      (node (ref "Q8") (pin "2") (pinfunction "E_2") (pintype "passive"))
    )
    (net (code "66") (name "Net-(D15-A)") (class "Default")
      (node (ref "D15") (pin "1") (pinfunction "A_1") (pintype "passive"))
      (node (ref "Q2") (pin "1") (pinfunction "B_1") (pintype "passive"))
      (node (ref "R34") (pin "2") (pinfunction "2_2") (pintype "passive"))
      (node (ref "R35") (pin "1") (pinfunction "1_1") (pintype "passive"))
    )
    (net (code "67") (name "Net-(D15-K)") (class "Default")
      (node (ref "C45") (pin "1") (pinfunction "1_1") (pintype "passive"))
      (node (ref "D15") (pin "3") (pinfunction "K_3") (pintype "passive"))
      (node (ref "J5") (pin "1") (pinfunction "1_1") (pintype "passive"))
      (node (ref "Q2") (pin "2") (pinfunction "E_2") (pintype "passive"))
      (node (ref "R34") (pin "1") (pinfunction "1_1") (pintype "passive"))
      (node (ref "R41") (pin "1") (pinfunction "1_1") (pintype "passive"))
    )
    (net (code "68") (name "Net-(D16-A)") (class "Default")
      (node (ref "D16") (pin "1") (pinfunction "A_1") (pintype "passive"))
      (node (ref "R32") (pin "1") (pinfunction "1_1") (pintype "passive"))
    )
    (net (code "69") (name "Net-(D16-K)") (class "Default")
      (node (ref "D16") (pin "2") (pinfunction "K_2") (pintype "passive"))
      (node (ref "D17") (pin "2") (pinfunction "K_2") (pintype "passive"))
      (node (ref "Q3") (pin "2") (pinfunction "E_2") (pintype "passive"))
      (node (ref "R36") (pin "2") (pinfunction "2_2") (pintype "passive"))
    )
    (net (code "70") (name "Net-(D17-A)") (class "Default")
      (node (ref "D17") (pin "1") (pinfunction "A_1") (pintype "passive"))
      (node (ref "R38") (pin "2") (pinfunction "2_2") (pintype "passive"))
    )
    (net (code "71") (name "Net-(D18-K)") (class "Default")
      (node (ref "C37") (pin "2") (pinfunction "2_2") (pintype "passive"))
      (node (ref "D18") (pin "2") (pinfunction "K_2") (pintype "passive"))
      (node (ref "L1") (pin "1") (pinfunction "1_1") (pintype "passive"))
    )
    (net (code "72") (name "Net-(D20-A)") (class "Default")
      (node (ref "D20") (pin "1") (pinfunction "A_1") (pintype "passive"))
      (node (ref "D22") (pin "1") (pinfunction "A_1") (pintype "passive"))
    )
    (net (code "73") (name "Net-(D20-K)") (class "Default")
      (node (ref "D20") (pin "3") (pinfunction "K_3") (pintype "passive"))
      (node (ref "R41") (pin "2") (pinfunction "2_2") (pintype "passive"))
      (node (ref "R42") (pin "1") (pinfunction "1_1") (pintype "passive"))
    )
    (net (code "74") (name "Net-(D22-K)") (class "Default")
      (node (ref "C45") (pin "2") (pinfunction "2_2") (pintype "passive"))
      (node (ref "D22") (pin "3") (pinfunction "K_3") (pintype "passive"))
      (node (ref "J5") (pin "2") (pinfunction "2_2") (pintype "passive"))
      (node (ref "Q16") (pin "3") (pinfunction "C_3") (pintype "passive"))
      (node (ref "R50") (pin "1") (pinfunction "1_1") (pintype "passive"))
    )
    (net (code "75") (name "Net-(D23-A)") (class "Default")
      (node (ref "D23") (pin "1") (pinfunction "A_1") (pintype "passive"))
      (node (ref "Q14") (pin "2") (pinfunction "E_2") (pintype "passive"))
    )
    (net (code "76") (name "Net-(Q2-C)") (class "Default")
      (node (ref "Q2") (pin "3") (pinfunction "C_3") (pintype "passive"))
      (node (ref "R31") (pin "1") (pinfunction "1_1") (pintype "passive"))
    )
    (net (code "77") (name "Net-(Q3-B)") (class "Default")
      (node (ref "Q3") (pin "1") (pinfunction "B_1") (pintype "passive"))
      (node (ref "Q6") (pin "3") (pinfunction "C_3") (pintype "passive"))
      (node (ref "R36") (pin "1") (pinfunction "1_1") (pintype "passive"))
    )
    (net (code "78") (name "Net-(Q4-B)") (class "Default")
      (node (ref "Q4") (pin "1") (pinfunction "B_1") (pintype "passive"))
      (node (ref "Q5") (pin "1") (pinfunction "B_1") (pintype "passive"))
      (node (ref "Q9") (pin "3") (pinfunction "C_3") (pintype "passive"))
      (node (ref "R44") (pin "1") (pinfunction "1_1") (pintype "passive"))
    )
    (net (code "79") (name "Net-(Q4-C)") (class "Default")
      (node (ref "Q4") (pin "3") (pinfunction "C_3") (pintype "passive"))
      (node (ref "Q5") (pin "3") (pinfunction "C_3") (pintype "passive"))
    )
    (net (code "80") (name "Net-(Q7-C)") (class "Default")
      (node (ref "Q7") (pin "3") (pinfunction "C_3") (pintype "passive"))
      (node (ref "R35") (pin "2") (pinfunction "2_2") (pintype "passive"))
    )
    (net (code "81") (name "Net-(Q10-B)") (class "Default")
      (node (ref "Q10") (pin "1") (pinfunction "B_1") (pintype "passive"))
      (node (ref "R54") (pin "1") (pinfunction "1_1") (pintype "passive"))
      (node (ref "R55") (pin "2") (pinfunction "2_2") (pintype "passive"))
    )
    (net (code "82") (name "Net-(Q10-C)") (class "Default")
      (node (ref "Q10") (pin "3") (pinfunction "C_3") (pintype "passive"))
      (node (ref "R50") (pin "2") (pinfunction "2_2") (pintype "passive"))
    )
    (net (code "83") (name "Net-(Q11-C)") (class "Default")
      (node (ref "Q11") (pin "3") (pinfunction "C_3") (pintype "passive"))
      (node (ref "R51") (pin "1") (pinfunction "1_1") (pintype "passive"))
    )
    (net (code "84") (name "Net-(Q12-C)") (class "Default")
      (node (ref "Q12") (pin "3") (pinfunction "C_3") (pintype "passive"))
      (node (ref "R52") (pin "1") (pinfunction "1_1") (pintype "passive"))
    )
    (net (code "85") (name "Net-(Q13-C)") (class "Default")
      (node (ref "Q13") (pin "3") (pinfunction "C_3") (pintype "passive"))
      (node (ref "R53") (pin "1") (pinfunction "1_1") (pintype "passive"))
    )
    (net (code "86") (name "Net-(Q14-B)") (class "Default")
      (node (ref "C41") (pin "2") (pinfunction "2_2") (pintype "passive"))
      (node (ref "Q14") (pin "1") (pinfunction "B_1") (pintype "passive"))
      (node (ref "Q9") (pin "1") (pinfunction "B_1") (pintype "passive"))
      (node (ref "R43") (pin "1") (pinfunction "1_1") (pintype "passive"))
      (node (ref "U10") (pin "4") (pintype "passive"))
    )
    (net (code "87") (name "Net-(Q15-B)") (class "Default")
      (node (ref "Q15") (pin "1") (pinfunction "B_1") (pintype "passive"))
      (node (ref "Q7") (pin "1") (pinfunction "B_1") (pintype "passive"))
      (node (ref "Q8") (pin "3") (pinfunction "C_3") (pintype "passive"))
      (node (ref "R33") (pin "1") (pinfunction "1_1") (pintype "passive"))
    )
    (net (code "88") (name "Net-(Q15-C)") (class "Default")
      (node (ref "Q15") (pin "3") (pinfunction "C_3") (pintype "passive"))
      (node (ref "R55") (pin "1") (pinfunction "1_1") (pintype "passive"))
    )
    (net (code "89") (name "Net-(R45-Pad2)") (class "Default")
      (node (ref "R45") (pin "2") (pinfunction "2_2") (pintype "passive"))
      (node (ref "U10") (pin "1") (pintype "passive"))
    )
    (net (code "90") (name "Net-(R47-Pad1)") (class "Default")
      (node (ref "R47") (pin "1") (pinfunction "1_1") (pintype "passive"))
      (node (ref "R51") (pin "2") (pinfunction "2_2") (pintype "passive"))
    )
    (net (code "91") (name "Net-(R48-Pad1)") (class "Default")
      (node (ref "R48") (pin "1") (pinfunction "1_1") (pintype "passive"))
      (node (ref "R52") (pin "2") (pinfunction "2_2") (pintype "passive"))
    )
    (net (code "92") (name "Net-(R49-Pad1)") (class "Default")
      (node (ref "R49") (pin "1") (pinfunction "1_1") (pintype "passive"))
      (node (ref "R53") (pin "2") (pinfunction "2_2") (pintype "passive"))
    )
    (net (code "93") (name "Net-(U7-CREF)") (class "Default")
      (node (ref "C25") (pin "1") (pinfunction "1_1") (pintype "passive"))
      (node (ref "U7") (pin "24") (pinfunction "CREF_24") (pintype "passive"))
    )
    (net (code "94") (name "Net-(U7-VCC)") (class "Default")
      (node (ref "C27") (pin "1") (pinfunction "1_1") (pintype "passive"))
      (node (ref "U7") (pin "17") (pinfunction "VCC_17") (pintype "passive"))
    )
    (net (code "95") (name "Net-(U8-CREF)") (class "Default")
      (node (ref "C26") (pin "1") (pinfunction "1_1") (pintype "passive"))
      (node (ref "U8") (pin "24") (pinfunction "CREF_24") (pintype "passive"))
    )
    (net (code "96") (name "Net-(U8-VCC)") (class "Default")
      (node (ref "C28") (pin "1") (pinfunction "1_1") (pintype "passive"))
      (node (ref "U8") (pin "17") (pinfunction "VCC_17") (pintype "passive"))
    )
    (net (code "97") (name "Net-(U9-CB)") (class "Default")
      (node (ref "C37") (pin "1") (pinfunction "1_1") (pintype "passive"))
      (node (ref "U9") (pin "1") (pinfunction "CB_1") (pintype "passive"))
      (node (ref "U9") (pin "6") (pinfunction "SW_6") (pintype "passive"))
    )
    (net (code "98") (name "Net-(U9-FB)") (class "Default")
      (node (ref "R40") (pin "1") (pinfunction "1_1") (pintype "passive"))
      (node (ref "R46") (pin "2") (pinfunction "2_2") (pintype "passive"))
      (node (ref "U9") (pin "3") (pinfunction "FB_3") (pintype "passive"))
    )
    (net (code "99") (name "VBL") (class "Default")
      (node (ref "Q3") (pin "3") (pinfunction "C_3") (pintype "passive"))
    )
    (net (code "100") (name "VCC") (class "Default")
      (node (ref "C42") (pin "1") (pinfunction "1_1") (pintype "passive"))
      (node (ref "C43") (pin "1") (pinfunction "1_1") (pintype "passive"))
      (node (ref "D23") (pin "2") (pinfunction "K_2") (pintype "passive"))
      (node (ref "Q5") (pin "2") (pinfunction "E_2") (pintype "passive"))
      (node (ref "U9") (pin "4") (pinfunction "SHDN_4") (pintype "passive"))
      (node (ref "U9") (pin "5") (pinfunction "VIN_5") (pintype "passive"))
    )
    (net (code "101") (name "VUSB") (class "Default")
      (node (ref "C46") (pin "1") (pinfunction "1_1") (pintype "passive"))
      (node (ref "Q14") (pin "3") (pinfunction "C_3") (pintype "passive"))
      (node (ref "R38") (pin "1") (pinfunction "1_1") (pintype "passive"))
      (node (ref "R45") (pin "1") (pinfunction "1_1") (pintype "passive"))
    )
  )
)
